# Power_Supply.net
KiCad netlist of a schematic drawn in Altium Designer
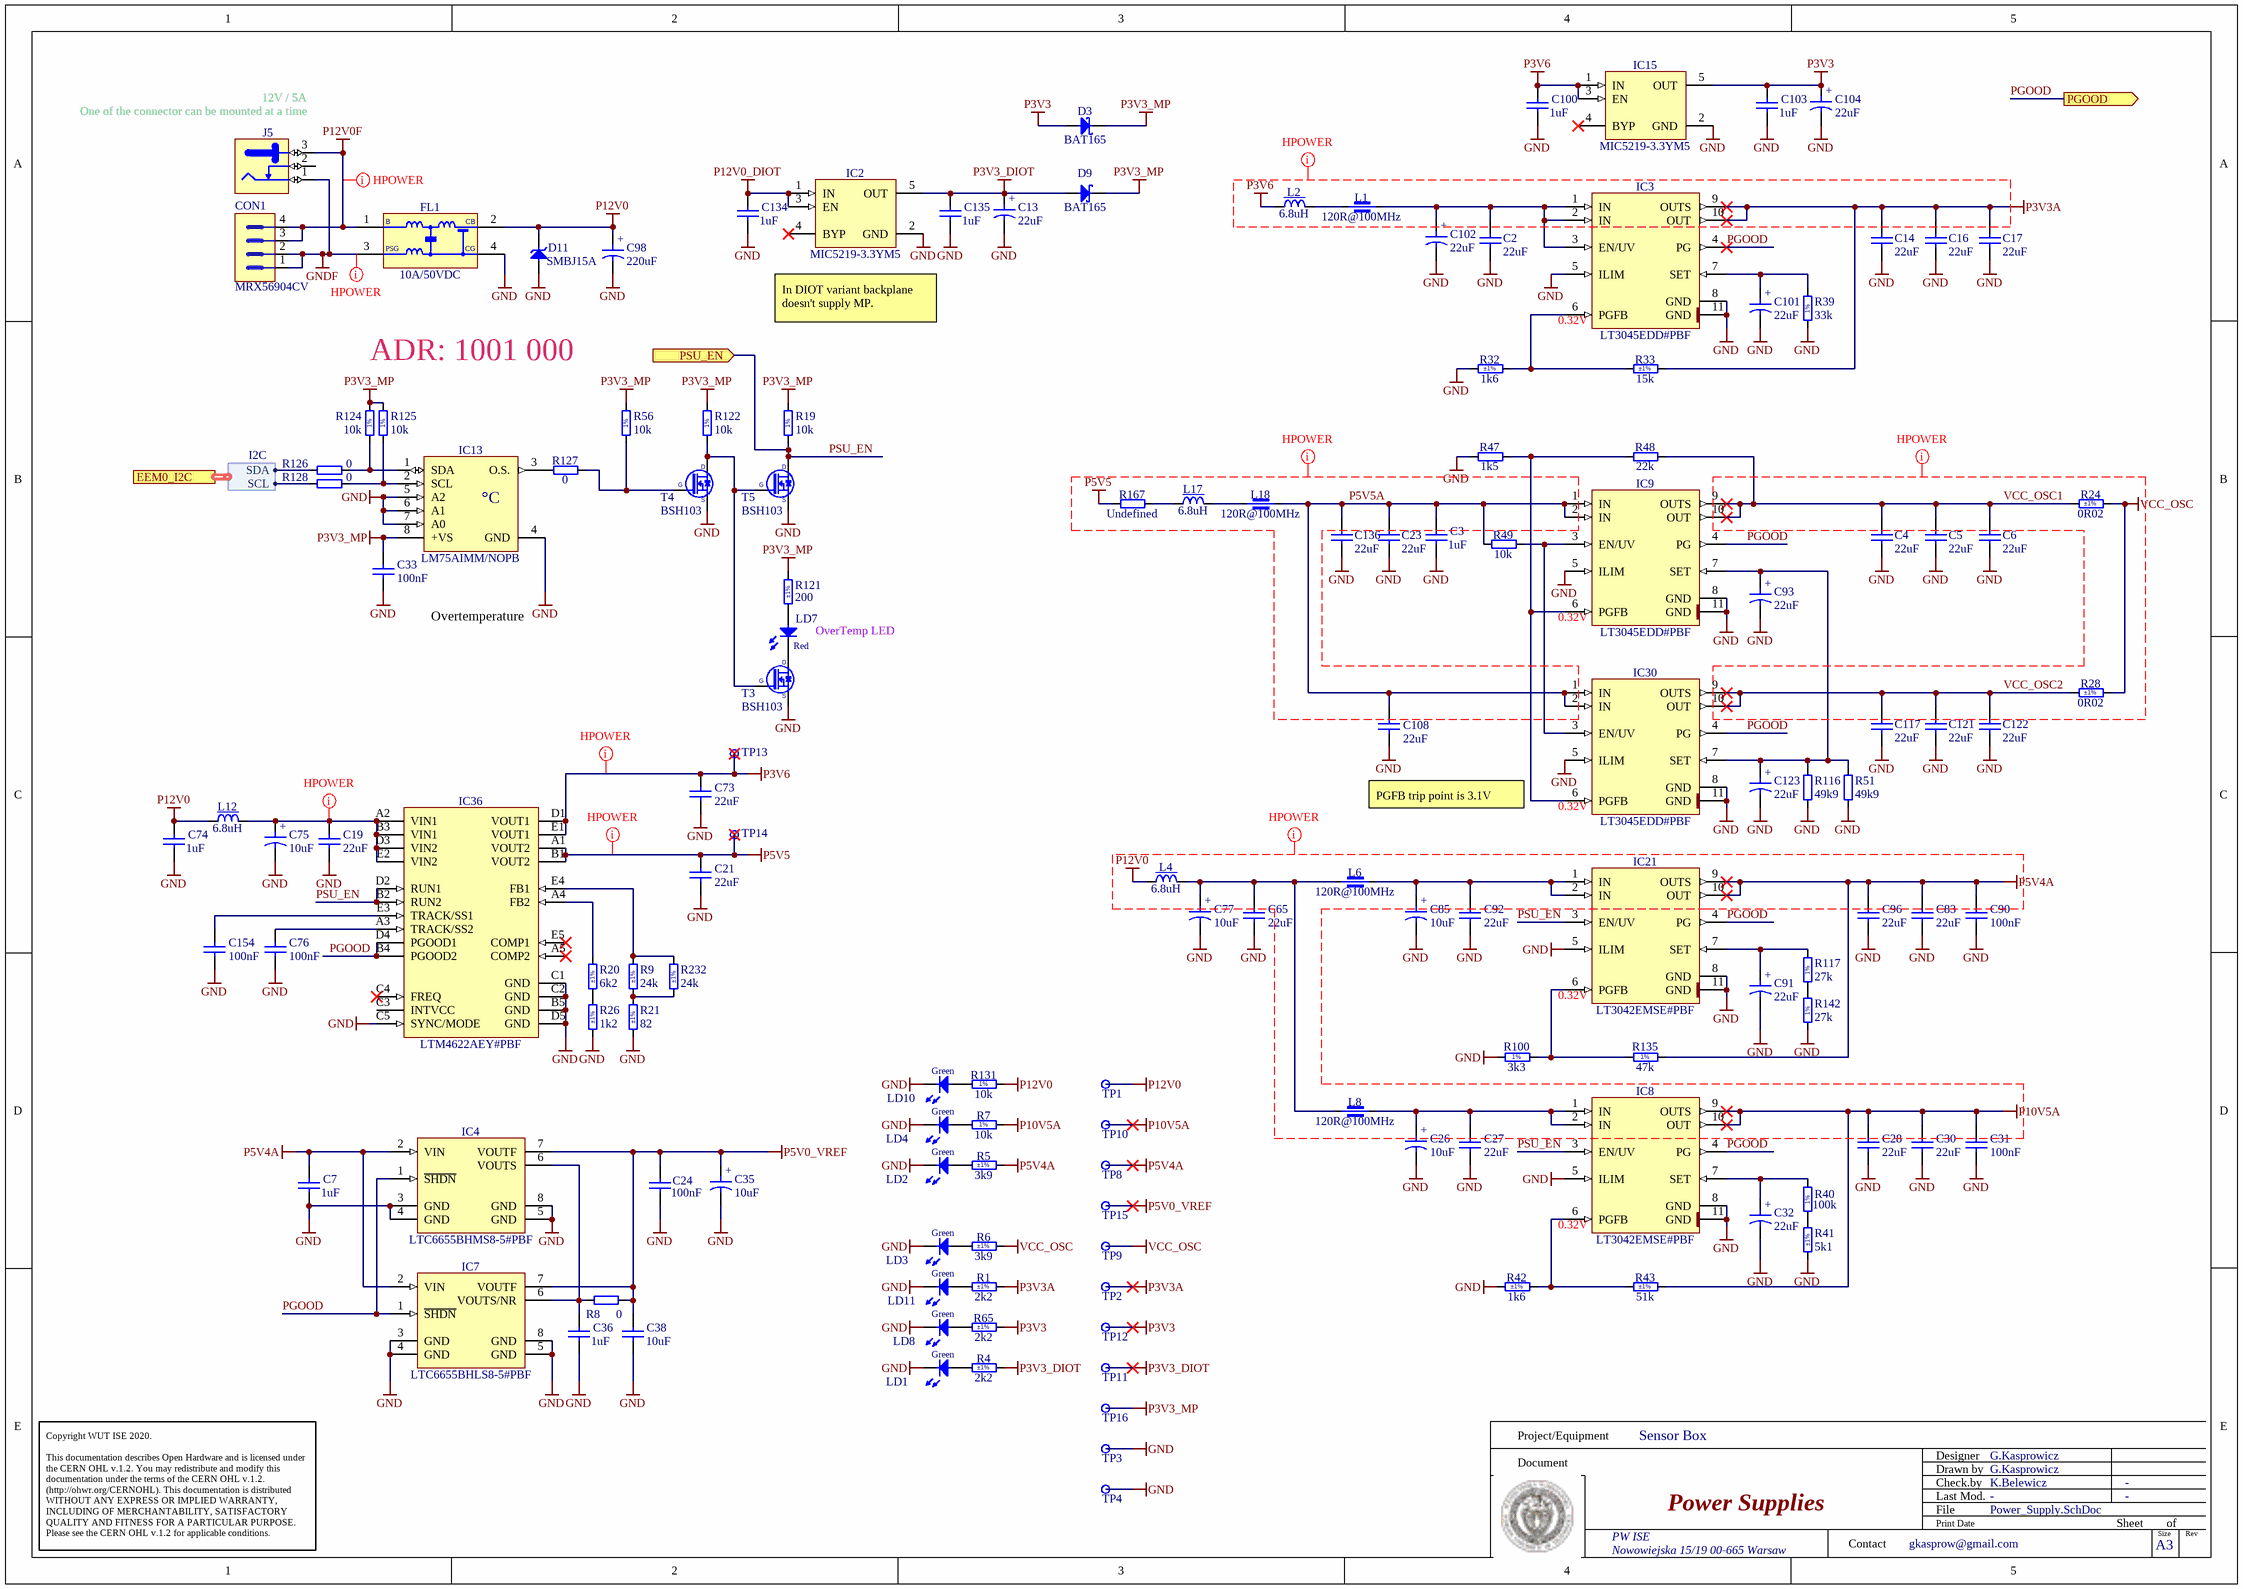
[diagram p0: Power_Supply.SchDoc]

(export (version "E")
  (design (tool "Eeschema 10.0.6"))
  (components
    (comp (ref "C2")
      (value "22uF")
      (footprint "CAPC2012X135N")
      (description "Non-polarised capacitor")
      (fields
        (field (name "PART NUMBER") "CC0805_22UF_16V_10%_X5R")
        (field (name "VOLTAGE") "16V")
        (field (name "AUTHOR") "CERN DEM JLC")
      )
      (libsource (lib "Capacitors") (part "Capacitor - non polarized"))
    )
    (comp (ref "C3")
      (value "1uF")
      (footprint "CAPC1005X55N")
      (description "Non-polarised capacitor")
      (fields
        (field (name "PART NUMBER") "CC0402_1UF_16V_10%_X5R")
        (field (name "VOLTAGE") "16V")
        (field (name "AUTHOR") "CERN DEM JLC")
      )
      (libsource (lib "Capacitors") (part "Capacitor - non polarized"))
    )
    (comp (ref "C4")
      (value "22uF")
      (footprint "CAPC2012X135N")
      (description "Non-polarised capacitor")
      (fields
        (field (name "PART NUMBER") "CC0805_22UF_16V_10%_X5R")
        (field (name "VOLTAGE") "16V")
        (field (name "AUTHOR") "CERN DEM JLC")
      )
      (libsource (lib "Capacitors") (part "Capacitor - non polarized"))
    )
    (comp (ref "C5")
      (value "22uF")
      (footprint "CAPC2012X135N")
      (description "Non-polarised capacitor")
      (fields
        (field (name "PART NUMBER") "CC0805_22UF_16V_10%_X5R")
        (field (name "VOLTAGE") "16V")
        (field (name "AUTHOR") "CERN DEM JLC")
      )
      (libsource (lib "Capacitors") (part "Capacitor - non polarized"))
    )
    (comp (ref "C6")
      (value "22uF")
      (footprint "CAPC2012X135N")
      (description "Non-polarised capacitor")
      (fields
        (field (name "PART NUMBER") "CC0805_22UF_16V_10%_X5R")
        (field (name "VOLTAGE") "16V")
        (field (name "AUTHOR") "CERN DEM JLC")
      )
      (libsource (lib "Capacitors") (part "Capacitor - non polarized"))
    )
    (comp (ref "C7")
      (value "1uF")
      (footprint "CAPC1005X55N")
      (description "Non-polarised capacitor")
      (fields
        (field (name "PART NUMBER") "CC0402_1UF_16V_10%_X5R")
        (field (name "VOLTAGE") "16V")
        (field (name "AUTHOR") "CERN DEM JLC")
      )
      (libsource (lib "Capacitors") (part "Capacitor - non polarized"))
    )
    (comp (ref "C13")
      (value "22uF")
      (footprint "CAPMP3528X210N")
      (description "Polarised capacitor")
      (fields
        (field (name "PART NUMBER") "CTE3528-21_22UF_10V_10%_LESR0700")
        (field (name "VOLTAGE") "10V")
        (field (name "AUTHOR") "CERN DEM JLC")
      )
      (libsource (lib "Capacitors") (part "Capacitor - polarized"))
    )
    (comp (ref "C14")
      (value "22uF")
      (footprint "CAPC2012X135N")
      (description "Non-polarised capacitor")
      (fields
        (field (name "PART NUMBER") "CC0805_22UF_16V_10%_X5R")
        (field (name "VOLTAGE") "16V")
        (field (name "AUTHOR") "CERN DEM JLC")
      )
      (libsource (lib "Capacitors") (part "Capacitor - non polarized"))
    )
    (comp (ref "C16")
      (value "22uF")
      (footprint "CAPC2012X135N")
      (description "Non-polarised capacitor")
      (fields
        (field (name "PART NUMBER") "CC0805_22UF_16V_10%_X5R")
        (field (name "VOLTAGE") "16V")
        (field (name "AUTHOR") "CERN DEM JLC")
      )
      (libsource (lib "Capacitors") (part "Capacitor - non polarized"))
    )
    (comp (ref "C17")
      (value "22uF")
      (footprint "CAPC2012X135N")
      (description "Non-polarised capacitor")
      (fields
        (field (name "PART NUMBER") "CC0805_22UF_16V_10%_X5R")
        (field (name "VOLTAGE") "16V")
        (field (name "AUTHOR") "CERN DEM JLC")
      )
      (libsource (lib "Capacitors") (part "Capacitor - non polarized"))
    )
    (comp (ref "C19")
      (value "22uF")
      (footprint "CAPC2012X135N")
      (description "Non-polarised capacitor")
      (fields
        (field (name "PART NUMBER") "CC0805_22UF_16V_10%_X5R")
        (field (name "VOLTAGE") "16V")
        (field (name "AUTHOR") "CERN DEM JLC")
      )
      (libsource (lib "Capacitors") (part "Capacitor - non polarized"))
    )
    (comp (ref "C21")
      (value "22uF")
      (footprint "CAPC2012X135N")
      (description "Non-polarised capacitor")
      (fields
        (field (name "PART NUMBER") "CC0805_22UF_16V_10%_X5R")
        (field (name "VOLTAGE") "16V")
        (field (name "AUTHOR") "CERN DEM JLC")
      )
      (libsource (lib "Capacitors") (part "Capacitor - non polarized"))
    )
    (comp (ref "C23")
      (value "22uF")
      (footprint "CAPC2012X135N")
      (description "Non-polarised capacitor")
      (fields
        (field (name "PART NUMBER") "CC0805_22UF_16V_10%_X5R")
        (field (name "VOLTAGE") "16V")
        (field (name "AUTHOR") "CERN DEM JLC")
      )
      (libsource (lib "Capacitors") (part "Capacitor - non polarized"))
    )
    (comp (ref "C24")
      (value "100nF")
      (footprint "CAPC1005X55N")
      (description "Non-polarised capacitor")
      (fields
        (field (name "PART NUMBER") "CC0402_100NF_16V_10%_X5R")
        (field (name "VOLTAGE") "16V")
        (field (name "AUTHOR") "CERN DEM JLC")
      )
      (libsource (lib "Capacitors") (part "Capacitor - non polarized"))
    )
    (comp (ref "C26")
      (value "10uF")
      (footprint "CAPMP3216X180N")
      (description "Polarised capacitor")
      (fields
        (field (name "PART NUMBER") "CTE3216-18_10UF_16V_20%_AVX_TCJ")
        (field (name "VOLTAGE") "16V")
        (field (name "AUTHOR") "CERN DEM JLC")
      )
      (libsource (lib "Capacitors") (part "Capacitor - polarized"))
    )
    (comp (ref "C27")
      (value "22uF")
      (footprint "CAPC2012X135N")
      (description "Non-polarised capacitor")
      (fields
        (field (name "PART NUMBER") "CC0805_22UF_16V_10%_X5R")
        (field (name "VOLTAGE") "16V")
        (field (name "AUTHOR") "CERN DEM JLC")
      )
      (libsource (lib "Capacitors") (part "Capacitor - non polarized"))
    )
    (comp (ref "C28")
      (value "22uF")
      (footprint "CAPC2012X135N")
      (description "Non-polarised capacitor")
      (fields
        (field (name "PART NUMBER") "CC0805_22UF_16V_10%_X5R")
        (field (name "VOLTAGE") "16V")
        (field (name "AUTHOR") "CERN DEM JLC")
      )
      (libsource (lib "Capacitors") (part "Capacitor - non polarized"))
    )
    (comp (ref "C30")
      (value "22uF")
      (footprint "CAPC2012X135N")
      (description "Non-polarised capacitor")
      (fields
        (field (name "PART NUMBER") "CC0805_22UF_16V_10%_X5R")
        (field (name "VOLTAGE") "16V")
        (field (name "AUTHOR") "CERN DEM JLC")
      )
      (libsource (lib "Capacitors") (part "Capacitor - non polarized"))
    )
    (comp (ref "C31")
      (value "100nF")
      (footprint "CAPC1005X55N")
      (description "Non-polarised capacitor")
      (fields
        (field (name "PART NUMBER") "CC0402_100NF_16V_10%_X5R")
        (field (name "VOLTAGE") "16V")
        (field (name "AUTHOR") "CERN DEM JLC")
      )
      (libsource (lib "Capacitors") (part "Capacitor - non polarized"))
    )
    (comp (ref "C32")
      (value "22uF")
      (footprint "CAPMP3528X210N")
      (description "Polarised capacitor")
      (fields
        (field (name "PART NUMBER") "CTE3528-21_22UF_10V_10%_LESR0700")
        (field (name "VOLTAGE") "10V")
        (field (name "AUTHOR") "CERN DEM JLC")
      )
      (libsource (lib "Capacitors") (part "Capacitor - polarized"))
    )
    (comp (ref "C33")
      (value "100nF")
      (footprint "CAPC1005X55N")
      (description "Non-polarised capacitor")
      (fields
        (field (name "PART NUMBER") "CC0402_100NF_16V_10%_X5R")
        (field (name "VOLTAGE") "16V")
        (field (name "AUTHOR") "CERN DEM JLC")
      )
      (libsource (lib "Capacitors") (part "Capacitor - non polarized"))
    )
    (comp (ref "C35")
      (value "10uF")
      (footprint "CAPMP3216X180N")
      (description "Polarised capacitor")
      (fields
        (field (name "PART NUMBER") "CTE3216-18_10UF_16V_20%_AVX_TCJ")
        (field (name "VOLTAGE") "16V")
        (field (name "AUTHOR") "CERN DEM JLC")
      )
      (libsource (lib "Capacitors") (part "Capacitor - polarized"))
    )
    (comp (ref "C36")
      (value "1uF")
      (footprint "CAPC1005X55N")
      (description "Non-polarised capacitor")
      (fields
        (field (name "PART NUMBER") "CC0402_1UF_16V_10%_X5R")
        (field (name "VOLTAGE") "16V")
        (field (name "AUTHOR") "CERN DEM JLC")
      )
      (libsource (lib "Capacitors") (part "Capacitor - non polarized"))
    )
    (comp (ref "C38")
      (value "10uF")
      (footprint "CAPC1608X80N")
      (description "Non-polarised capacitor")
      (fields
        (field (name "PART NUMBER") "CC0603_10UF_16V_20%_X5R")
        (field (name "VOLTAGE") "16V")
        (field (name "AUTHOR") "CERN DEM MR")
      )
      (libsource (lib "Capacitors") (part "Capacitor - non polarized"))
    )
    (comp (ref "C65")
      (value "22uF")
      (footprint "CAPC2012X135N")
      (description "Non-polarised capacitor")
      (fields
        (field (name "PART NUMBER") "CC0805_22UF_16V_10%_X5R")
        (field (name "VOLTAGE") "16V")
        (field (name "AUTHOR") "CERN DEM JLC")
      )
      (libsource (lib "Capacitors") (part "Capacitor - non polarized"))
    )
    (comp (ref "C73")
      (value "22uF")
      (footprint "CAPC2012X135N")
      (description "Non-polarised capacitor")
      (fields
        (field (name "PART NUMBER") "CC0805_22UF_16V_10%_X5R")
        (field (name "VOLTAGE") "16V")
        (field (name "AUTHOR") "CERN DEM JLC")
      )
      (libsource (lib "Capacitors") (part "Capacitor - non polarized"))
    )
    (comp (ref "C74")
      (value "1uF")
      (footprint "CAPC1005X55N")
      (description "Non-polarised capacitor")
      (fields
        (field (name "PART NUMBER") "CC0402_1UF_16V_10%_X5R")
        (field (name "VOLTAGE") "16V")
        (field (name "AUTHOR") "CERN DEM JLC")
      )
      (libsource (lib "Capacitors") (part "Capacitor - non polarized"))
    )
    (comp (ref "C75")
      (value "10uF")
      (footprint "CAPMP3216X180N")
      (description "Polarised capacitor")
      (fields
        (field (name "PART NUMBER") "CTE3216-18_10UF_16V_20%_AVX_TCJ")
        (field (name "VOLTAGE") "16V")
        (field (name "AUTHOR") "CERN DEM JLC")
      )
      (libsource (lib "Capacitors") (part "Capacitor - polarized"))
    )
    (comp (ref "C76")
      (value "100nF")
      (footprint "CAPC1005X55N")
      (description "Non-polarised capacitor")
      (fields
        (field (name "PART NUMBER") "CC0402_100NF_16V_10%_X5R")
        (field (name "VOLTAGE") "16V")
        (field (name "AUTHOR") "CERN DEM JLC")
      )
      (libsource (lib "Capacitors") (part "Capacitor - non polarized"))
    )
    (comp (ref "C77")
      (value "10uF")
      (footprint "CAPMP3216X180N")
      (description "Polarised capacitor")
      (fields
        (field (name "PART NUMBER") "CTE3216-18_10UF_16V_20%_AVX_TCJ")
        (field (name "VOLTAGE") "16V")
        (field (name "AUTHOR") "CERN DEM JLC")
      )
      (libsource (lib "Capacitors") (part "Capacitor - polarized"))
    )
    (comp (ref "C83")
      (value "22uF")
      (footprint "CAPC2012X135N")
      (description "Non-polarised capacitor")
      (fields
        (field (name "PART NUMBER") "CC0805_22UF_16V_10%_X5R")
        (field (name "VOLTAGE") "16V")
        (field (name "AUTHOR") "CERN DEM JLC")
      )
      (libsource (lib "Capacitors") (part "Capacitor - non polarized"))
    )
    (comp (ref "C85")
      (value "10uF")
      (footprint "CAPMP3216X180N")
      (description "Polarised capacitor")
      (fields
        (field (name "PART NUMBER") "CTE3216-18_10UF_16V_20%_AVX_TCJ")
        (field (name "VOLTAGE") "16V")
        (field (name "AUTHOR") "CERN DEM JLC")
      )
      (libsource (lib "Capacitors") (part "Capacitor - polarized"))
    )
    (comp (ref "C90")
      (value "100nF")
      (footprint "CAPC1005X55N")
      (description "Non-polarised capacitor")
      (fields
        (field (name "PART NUMBER") "CC0402_100NF_16V_10%_X5R")
        (field (name "VOLTAGE") "16V")
        (field (name "AUTHOR") "CERN DEM JLC")
      )
      (libsource (lib "Capacitors") (part "Capacitor - non polarized"))
    )
    (comp (ref "C91")
      (value "22uF")
      (footprint "CAPMP3528X210N")
      (description "Polarised capacitor")
      (fields
        (field (name "PART NUMBER") "CTE3528-21_22UF_10V_10%_LESR0700")
        (field (name "VOLTAGE") "10V")
        (field (name "AUTHOR") "CERN DEM JLC")
      )
      (libsource (lib "Capacitors") (part "Capacitor - polarized"))
    )
    (comp (ref "C92")
      (value "22uF")
      (footprint "CAPC2012X135N")
      (description "Non-polarised capacitor")
      (fields
        (field (name "PART NUMBER") "CC0805_22UF_16V_10%_X5R")
        (field (name "VOLTAGE") "16V")
        (field (name "AUTHOR") "CERN DEM JLC")
      )
      (libsource (lib "Capacitors") (part "Capacitor - non polarized"))
    )
    (comp (ref "C93")
      (value "22uF")
      (footprint "CAPMP3528X210N")
      (description "Polarised capacitor")
      (fields
        (field (name "PART NUMBER") "CTE3528-21_22UF_10V_10%_LESR0700")
        (field (name "VOLTAGE") "10V")
        (field (name "AUTHOR") "CERN DEM JLC")
      )
      (libsource (lib "Capacitors") (part "Capacitor - polarized"))
    )
    (comp (ref "C96")
      (value "22uF")
      (footprint "CAPC2012X135N")
      (description "Non-polarised capacitor")
      (fields
        (field (name "PART NUMBER") "CC0805_22UF_16V_10%_X5R")
        (field (name "VOLTAGE") "16V")
        (field (name "AUTHOR") "CERN DEM JLC")
      )
      (libsource (lib "Capacitors") (part "Capacitor - non polarized"))
    )
    (comp (ref "C98")
      (value "220uF")
      (footprint "CAPAE830X620N")
      (description "Polarised capacitor")
      (fields
        (field (name "PART NUMBER") "CAE830-620_220UF_16V_20%")
        (field (name "VOLTAGE") "16V")
        (field (name "AUTHOR") "CERN DEM JLC")
      )
      (libsource (lib "Capacitors") (part "Capacitor - polarized"))
    )
    (comp (ref "C100")
      (value "1uF")
      (footprint "CAPC1005X55N")
      (description "Non-polarised capacitor")
      (fields
        (field (name "PART NUMBER") "CC0402_1UF_16V_10%_X5R")
        (field (name "VOLTAGE") "16V")
        (field (name "AUTHOR") "CERN DEM JLC")
      )
      (libsource (lib "Capacitors") (part "Capacitor - non polarized"))
    )
    (comp (ref "C101")
      (value "22uF")
      (footprint "CAPMP3528X210N")
      (description "Polarised capacitor")
      (fields
        (field (name "PART NUMBER") "CTE3528-21_22UF_10V_10%_LESR0700")
        (field (name "VOLTAGE") "10V")
        (field (name "AUTHOR") "CERN DEM JLC")
      )
      (libsource (lib "Capacitors") (part "Capacitor - polarized"))
    )
    (comp (ref "C102")
      (value "22uF")
      (footprint "CAPMP3528X210N")
      (description "Polarised capacitor")
      (fields
        (field (name "PART NUMBER") "CTE3528-21_22UF_10V_10%_LESR0700")
        (field (name "VOLTAGE") "10V")
        (field (name "AUTHOR") "CERN DEM JLC")
      )
      (libsource (lib "Capacitors") (part "Capacitor - polarized"))
    )
    (comp (ref "C103")
      (value "1uF")
      (footprint "CAPC1005X55N")
      (description "Non-polarised capacitor")
      (fields
        (field (name "PART NUMBER") "CC0402_1UF_16V_10%_X5R")
        (field (name "VOLTAGE") "16V")
        (field (name "AUTHOR") "CERN DEM JLC")
      )
      (libsource (lib "Capacitors") (part "Capacitor - non polarized"))
    )
    (comp (ref "C104")
      (value "22uF")
      (footprint "CAPMP3528X210N")
      (description "Polarised capacitor")
      (fields
        (field (name "PART NUMBER") "CTE3528-21_22UF_10V_10%_LESR0700")
        (field (name "VOLTAGE") "10V")
        (field (name "AUTHOR") "CERN DEM JLC")
      )
      (libsource (lib "Capacitors") (part "Capacitor - polarized"))
    )
    (comp (ref "C108")
      (value "22uF")
      (footprint "CAPC2012X135N")
      (description "Non-polarised capacitor")
      (fields
        (field (name "PART NUMBER") "CC0805_22UF_16V_10%_X5R")
        (field (name "VOLTAGE") "16V")
        (field (name "AUTHOR") "CERN DEM JLC")
      )
      (libsource (lib "Capacitors") (part "Capacitor - non polarized"))
    )
    (comp (ref "C117")
      (value "22uF")
      (footprint "CAPC2012X135N")
      (description "Non-polarised capacitor")
      (fields
        (field (name "PART NUMBER") "CC0805_22UF_16V_10%_X5R")
        (field (name "VOLTAGE") "16V")
        (field (name "AUTHOR") "CERN DEM JLC")
      )
      (libsource (lib "Capacitors") (part "Capacitor - non polarized"))
    )
    (comp (ref "C121")
      (value "22uF")
      (footprint "CAPC2012X135N")
      (description "Non-polarised capacitor")
      (fields
        (field (name "PART NUMBER") "CC0805_22UF_16V_10%_X5R")
        (field (name "VOLTAGE") "16V")
        (field (name "AUTHOR") "CERN DEM JLC")
      )
      (libsource (lib "Capacitors") (part "Capacitor - non polarized"))
    )
    (comp (ref "C122")
      (value "22uF")
      (footprint "CAPC2012X135N")
      (description "Non-polarised capacitor")
      (fields
        (field (name "PART NUMBER") "CC0805_22UF_16V_10%_X5R")
        (field (name "VOLTAGE") "16V")
        (field (name "AUTHOR") "CERN DEM JLC")
      )
      (libsource (lib "Capacitors") (part "Capacitor - non polarized"))
    )
    (comp (ref "C123")
      (value "22uF")
      (footprint "CAPMP3528X210N")
      (description "Polarised capacitor")
      (fields
        (field (name "PART NUMBER") "CTE3528-21_22UF_10V_10%_LESR0700")
        (field (name "VOLTAGE") "10V")
        (field (name "AUTHOR") "CERN DEM JLC")
      )
      (libsource (lib "Capacitors") (part "Capacitor - polarized"))
    )
    (comp (ref "C134")
      (value "1uF")
      (footprint "CAPC1005X55N")
      (description "Non-polarised capacitor")
      (fields
        (field (name "PART NUMBER") "CC0402_1UF_16V_10%_X5R")
        (field (name "VOLTAGE") "16V")
        (field (name "AUTHOR") "CERN DEM JLC")
      )
      (libsource (lib "Capacitors") (part "Capacitor - non polarized"))
    )
    (comp (ref "C135")
      (value "1uF")
      (footprint "CAPC1005X55N")
      (description "Non-polarised capacitor")
      (fields
        (field (name "PART NUMBER") "CC0402_1UF_16V_10%_X5R")
        (field (name "VOLTAGE") "16V")
        (field (name "AUTHOR") "CERN DEM JLC")
      )
      (libsource (lib "Capacitors") (part "Capacitor - non polarized"))
    )
    (comp (ref "C136")
      (value "22uF")
      (footprint "CAPC2012X135N")
      (description "Non-polarised capacitor")
      (fields
        (field (name "PART NUMBER") "CC0805_22UF_16V_10%_X5R")
        (field (name "VOLTAGE") "16V")
        (field (name "AUTHOR") "CERN DEM JLC")
      )
      (libsource (lib "Capacitors") (part "Capacitor - non polarized"))
    )
    (comp (ref "C154")
      (value "100nF")
      (footprint "CAPC1005X55N")
      (description "Non-polarised capacitor")
      (fields
        (field (name "PART NUMBER") "CC0402_100NF_16V_10%_X5R")
        (field (name "VOLTAGE") "16V")
        (field (name "AUTHOR") "CERN DEM JLC")
      )
      (libsource (lib "Capacitors") (part "Capacitor - non polarized"))
    )
    (comp (ref "CON1")
      (value "MRX56904CV")
      (footprint "MRX56904CV")
      (description "4.2mm cripm terminal header")
      (fields (field (name "MANUFACTURER") "Molex"))
      (libsource (lib "LIBRARY_SCH") (part "CON_CRIMP_4.2mm_RA_4"))
    )
    (comp (ref "D3")
      (value "BAT165")
      (footprint "SOD2512X110N")
      (description "Schottky Diode")
      (fields
        (field (name "VOLTAGE") "40V")
        (field (name "POWER") "750mA")
        (field (name "AUTHOR") "CERN DEM JLC")
      )
      (libsource (lib "ICs And Semiconductors") (part "Diode Schottky"))
    )
    (comp (ref "D9")
      (value "BAT165")
      (footprint "SOD2512X110N")
      (description "Schottky Diode")
      (fields
        (field (name "MANUFACTURER") "INFINEON")
        (field (name "VOLTAGE") "40V")
        (field (name "AUTHOR") "CERN DEM JLC")
      )
      (libsource (lib "ICs And Semiconductors") (part "Diode Schottky"))
    )
    (comp (ref "D11")
      (value "SMBJ15A")
      (footprint "DIOM5336X265N")
      (description "Zener Diode")
      (fields
        (field (name "VOLTAGE") "15V")
        (field (name "POWER") "600W")
        (field (name "AUTHOR") "CERN DEM JLC")
      )
      (libsource (lib "ICs And Semiconductors") (part "Diode Zener"))
    )
    (comp (ref "FL1")
      (value "10A/50VDC")
      (footprint "FIL_MURATA_BNX02")
      (description "Block Type EMIFIL (LC Combined)")
      (fields
        (field (name "PART NUMBER") "FIL_MURATA_BNX022-01L")
        (field (name "MANUFACTURER") "MURATA")
        (field (name "AUTHOR") "CERN DEM JLC")
      )
      (libsource (lib "Inductors & Transformers") (part "FIL_MURATA_BNX02"))
    )
    (comp (ref "IC2")
      (value "MIC5219-3.3YM5")
      (footprint "SOT95P280X145-5N")
      (description "500mA Peak Output LDO Regulator")
      (fields (field (name "MANUFACTURER") "MICROCHIP TECHNOLOGY") (field (name "AUTHOR") "CERN DEM WB"))
      (libsource (lib "ICs And Semiconductors") (part "MIC5219-X.XYM5"))
    )
    (comp (ref "IC3")
      (value "LT3045EDD#PBF")
      (footprint "SON50P300X300X80-11N-R175X248")
      (description "20V, 500mA, Ultralow Noise, Ultrahigh PSRR Linear Regulator")
      (fields (field (name "MANUFACTURER") "LINEAR TECHNOLOGY") (field (name "AUTHOR") "CERN DEM JLC"))
      (libsource (lib "ICs And Semiconductors") (part "LT3045EDD"))
    )
    (comp (ref "IC4")
      (value "LTC6655BHMS8-5#PBF")
      (footprint "SOP65P490X110-8N")
      (description "0.25ppm Noise, Low Drift Precision Buffered Voltage Reference")
      (fields (field (name "MANUFACTURER") "LINEAR TECHNOLOGY") (field (name "AUTHOR") "CERN DEM JLC"))
      (libsource (lib "ICs And Semiconductors") (part "LTC6655"))
    )
    (comp (ref "IC7")
      (value "LTC6655BHLS8-5#PBF")
      (footprint "8-CLCC")
      (description "5.0V, 1uA Precision Voltage Reference")
      (fields (field (name "MANUFACTURER") "LINEAR TECHNOLOGY") (field (name "AUTHOR") "GK"))
      (libsource (lib "Sampler") (part "REF_LTC6655CHLS8-4.096"))
    )
    (comp (ref "IC8")
      (value "LT3042EMSE#PBF")
      (footprint "SOP50P490X110-11N-R168X198")
      (description "20V, 200mA, Ultralow Noise, Ultrahigh PSRR RF Linear Regulator")
      (fields (field (name "MANUFACTURER") "LINEAR TECHNOLOGY") (field (name "AUTHOR") "CERN DEM MR"))
      (libsource (lib "ICs And Semiconductors") (part "LT3042"))
    )
    (comp (ref "IC9")
      (value "LT3045EDD#PBF")
      (footprint "SON50P300X300X80-11N-R175X248")
      (description "20V, 500mA, Ultralow Noise, Ultrahigh PSRR Linear Regulator")
      (fields (field (name "MANUFACTURER") "LINEAR TECHNOLOGY") (field (name "AUTHOR") "CERN DEM JLC"))
      (libsource (lib "ICs And Semiconductors") (part "LT3045EDD"))
    )
    (comp (ref "IC13")
      (value "LM75AIMM/NOPB")
      (footprint "SOP65P490X109-8N")
      (description "Digital Temperature Sensor and Thermal Watchdog with Two-Wire Interface")
      (fields (field (name "MANUFACTURER") "TEXAS INSTRUMENTS") (field (name "AUTHOR") "CERN DEM JLC"))
      (libsource (lib "ICs And Semiconductors") (part "LM75"))
    )
    (comp (ref "IC15")
      (value "MIC5219-3.3YM5")
      (footprint "SOT95P280X145-5N")
      (description "500mA Peak Output LDO Regulator")
      (fields (field (name "MANUFACTURER") "MICROCHIP TECHNOLOGY") (field (name "AUTHOR") "CERN DEM WB"))
      (libsource (lib "ICs And Semiconductors") (part "MIC5219-X.XYM5"))
    )
    (comp (ref "IC21")
      (value "LT3042EMSE#PBF")
      (footprint "SOP50P490X110-11N-R168X198")
      (description "20V, 200mA, Ultralow Noise, Ultrahigh PSRR RF Linear Regulator")
      (fields (field (name "MANUFACTURER") "LINEAR TECHNOLOGY") (field (name "AUTHOR") "CERN DEM MR"))
      (libsource (lib "ICs And Semiconductors") (part "LT3042"))
    )
    (comp (ref "IC30")
      (value "LT3045EDD#PBF")
      (footprint "SON50P300X300X80-11N-R175X248")
      (description "20V, 500mA, Ultralow Noise, Ultrahigh PSRR Linear Regulator")
      (fields (field (name "MANUFACTURER") "LINEAR TECHNOLOGY") (field (name "AUTHOR") "CERN DEM JLC"))
      (libsource (lib "ICs And Semiconductors") (part "LT3045EDD"))
    )
    (comp (ref "IC36")
      (value "LTM4622AEY#PBF")
      (footprint "BGA25C127P5X5_625X625X262")
      (description "3.6V-20V To 1.5V-12V, Dual 2A or Single 4A  Ultrathin Step-Down DC/DC µModule Regulator")
      (fields (field (name "MANUFACTURER") "LINEAR TECHNOLOGY") (field (name "AUTHOR") "CERN DEM MR"))
      (libsource (lib "ICs And Semiconductors") (part "LTM4622A"))
    )
    (comp (ref "J5")
      (value "Jack")
      (footprint "SWITCHCRAFT_L712RA")
      (description "24V /3. 5A, 2.1mm Diameter Pin, SMD DC Power Supply Connector With  Break Contact")
      (fields
        (field (name "PART NUMBER") "SWITCHCRAFT_L712RA")
        (field (name "MANUFACTURER") "SWITCHCRAFT")
        (field (name "AUTHOR") "GK")
      )
      (libsource (lib "LIBRARY_SCH") (part "CON_DC_5A_THT_RA"))
    )
    (comp (ref "L1")
      (value "120R@100MHz")
      (footprint "INDC1608X65N")
      (fields
        (field (name "PART NUMBER") "IND0603_MURATA_BLM18SG121TN1D")
        (field (name "POWER") "3A")
        (field (name "TOLERANCE") "±25%")
        (field (name "AUTHOR") "CERN DEM JLC")
      )
      (libsource (lib "Inductors & Transformers") (part "Ferrite Bead"))
    )
    (comp (ref "L2")
      (value "6.8uH")
      (footprint "IND_COILCRAFT_XAL4030")
      (description "Inductor With Core")
      (fields
        (field (name "PART NUMBER") "IND_6.8UH_20%_COILCRAFT_XAL4030")
        (field (name "POWER") "3A")
        (field (name "AUTHOR") "CERN DEM MR")
      )
      (libsource (lib "Inductors & Transformers") (part "Inductor With Magnetic core"))
    )
    (comp (ref "L4")
      (value "6.8uH")
      (footprint "IND_COILCRAFT_XAL4030")
      (description "Inductor With Core")
      (fields
        (field (name "PART NUMBER") "IND_6.8UH_20%_COILCRAFT_XAL4030")
        (field (name "POWER") "3A")
        (field (name "AUTHOR") "CERN DEM MR")
      )
      (libsource (lib "Inductors & Transformers") (part "Inductor With Magnetic core"))
    )
    (comp (ref "L6")
      (value "120R@100MHz")
      (footprint "INDC1608X65N")
      (fields
        (field (name "PART NUMBER") "IND0603_MURATA_BLM18SG121TN1D")
        (field (name "POWER") "3A")
        (field (name "TOLERANCE") "±25%")
        (field (name "AUTHOR") "CERN DEM JLC")
      )
      (libsource (lib "Inductors & Transformers") (part "Ferrite Bead"))
    )
    (comp (ref "L8")
      (value "120R@100MHz")
      (footprint "INDC1608X65N")
      (fields
        (field (name "PART NUMBER") "IND0603_MURATA_BLM18SG121TN1D")
        (field (name "POWER") "3A")
        (field (name "TOLERANCE") "±25%")
        (field (name "AUTHOR") "CERN DEM JLC")
      )
      (libsource (lib "Inductors & Transformers") (part "Ferrite Bead"))
    )
    (comp (ref "L12")
      (value "6.8uH")
      (footprint "IND_COILCRAFT_XAL4030")
      (description "Inductor With Core")
      (fields
        (field (name "PART NUMBER") "IND_6.8UH_20%_COILCRAFT_XAL4030")
        (field (name "POWER") "3A")
        (field (name "AUTHOR") "CERN DEM MR")
      )
      (libsource (lib "Inductors & Transformers") (part "Inductor With Magnetic core"))
    )
    (comp (ref "L17")
      (value "6.8uH")
      (footprint "IND_COILCRAFT_XAL4030")
      (description "Inductor With Core")
      (fields
        (field (name "PART NUMBER") "IND_6.8UH_20%_COILCRAFT_XAL4030")
        (field (name "POWER") "3A")
        (field (name "AUTHOR") "CERN DEM MR")
      )
      (libsource (lib "Inductors & Transformers") (part "Inductor With Magnetic core"))
    )
    (comp (ref "L18")
      (value "120R@100MHz")
      (footprint "INDC1608X65N")
      (fields
        (field (name "PART NUMBER") "IND0603_MURATA_BLM18SG121TN1D")
        (field (name "POWER") "3A")
        (field (name "TOLERANCE") "±25%")
        (field (name "AUTHOR") "CERN DEM JLC")
      )
      (libsource (lib "Inductors & Transformers") (part "Ferrite Bead"))
    )
    (comp (ref "LD1")
      (value "Green")
      (footprint "LED_KINGBRIGHT_KPH-1608CGCK")
      (description "LED Green 1C 2A")
      (fields
        (field (name "PART NUMBER") "LED_KINGBRIGHT_KPH-1608CGCK")
        (field (name "MANUFACTURER") "KINGBRIGHT")
        (field (name "AUTHOR") "CERN DEM JLC")
      )
      (libsource (lib "ICs And Semiconductors") (part "LED Green 1C 2A"))
    )
    (comp (ref "LD2")
      (value "Green")
      (footprint "LED_KINGBRIGHT_KPH-1608CGCK")
      (description "LED Green 1C 2A")
      (fields
        (field (name "PART NUMBER") "LED_KINGBRIGHT_KPH-1608CGCK")
        (field (name "MANUFACTURER") "KINGBRIGHT")
        (field (name "AUTHOR") "CERN DEM JLC")
      )
      (libsource (lib "ICs And Semiconductors") (part "LED Green 1C 2A"))
    )
    (comp (ref "LD3")
      (value "Green")
      (footprint "LED_KINGBRIGHT_KPH-1608CGCK")
      (description "LED Green 1C 2A")
      (fields
        (field (name "PART NUMBER") "LED_KINGBRIGHT_KPH-1608CGCK")
        (field (name "MANUFACTURER") "KINGBRIGHT")
        (field (name "AUTHOR") "CERN DEM JLC")
      )
      (libsource (lib "ICs And Semiconductors") (part "LED Green 1C 2A"))
    )
    (comp (ref "LD4")
      (value "Green")
      (footprint "LED_KINGBRIGHT_KPH-1608CGCK")
      (description "LED Green 1C 2A")
      (fields
        (field (name "PART NUMBER") "LED_KINGBRIGHT_KPH-1608CGCK")
        (field (name "MANUFACTURER") "KINGBRIGHT")
        (field (name "AUTHOR") "CERN DEM JLC")
      )
      (libsource (lib "ICs And Semiconductors") (part "LED Green 1C 2A"))
    )
    (comp (ref "LD7")
      (value "Red")
      (footprint "LED_DIALIGHT_555-200")
      (description "LED Red 1C 2A")
      (fields
        (field (name "PART NUMBER") "LED_DIALIGHT_555-2001F")
        (field (name "MANUFACTURER") "DIALIGHT")
        (field (name "AUTHOR") "CERN DEM JMW")
      )
      (libsource (lib "ICs And Semiconductors") (part "LED Red 1C 2A"))
    )
    (comp (ref "LD8")
      (value "Green")
      (footprint "LED_KINGBRIGHT_KPH-1608CGCK")
      (description "LED Green 1C 2A")
      (fields
        (field (name "PART NUMBER") "LED_KINGBRIGHT_KPH-1608CGCK")
        (field (name "MANUFACTURER") "KINGBRIGHT")
        (field (name "AUTHOR") "CERN DEM JLC")
      )
      (libsource (lib "ICs And Semiconductors") (part "LED Green 1C 2A"))
    )
    (comp (ref "LD10")
      (value "Green")
      (footprint "LED_KINGBRIGHT_KPH-1608CGCK")
      (description "LED Green 1C 2A")
      (fields
        (field (name "PART NUMBER") "LED_KINGBRIGHT_KPH-1608CGCK")
        (field (name "MANUFACTURER") "KINGBRIGHT")
        (field (name "AUTHOR") "CERN DEM JLC")
      )
      (libsource (lib "ICs And Semiconductors") (part "LED Green 1C 2A"))
    )
    (comp (ref "LD11")
      (value "Green")
      (footprint "LED_KINGBRIGHT_KPH-1608CGCK")
      (description "LED Green 1C 2A")
      (fields
        (field (name "PART NUMBER") "LED_KINGBRIGHT_KPH-1608CGCK")
        (field (name "MANUFACTURER") "KINGBRIGHT")
        (field (name "AUTHOR") "CERN DEM JLC")
      )
      (libsource (lib "ICs And Semiconductors") (part "LED Green 1C 2A"))
    )
    (comp (ref "R1")
      (value "2k2")
      (footprint "RESC1005X40N")
      (description "Resistor - 1%")
      (fields
        (field (name "TOLERANCE") "±1%")
        (field (name "PART NUMBER") "R0402_2K2_1%_0.0625W_100PPM")
        (field (name "POWER") "0.0625W")
        (field (name "AUTHOR") "CERN DEM JLC")
      )
      (libsource (lib "Resistors") (part "Resistor - 1%"))
    )
    (comp (ref "R4")
      (value "2k2")
      (footprint "RESC1005X40N")
      (description "Resistor - 1%")
      (fields
        (field (name "TOLERANCE") "±1%")
        (field (name "PART NUMBER") "R0402_2K2_1%_0.0625W_100PPM")
        (field (name "POWER") "0.0625W")
        (field (name "AUTHOR") "CERN DEM JLC")
      )
      (libsource (lib "Resistors") (part "Resistor - 1%"))
    )
    (comp (ref "R5")
      (value "3k9")
      (footprint "RESC1005X40N")
      (description "Resistor - 1%")
      (fields
        (field (name "TOLERANCE") "±1%")
        (field (name "PART NUMBER") "R0402_3K9_1%_0.0625W_100PPM")
        (field (name "POWER") "0.0625W")
        (field (name "AUTHOR") "CERN DEM JLC")
      )
      (libsource (lib "Resistors") (part "Resistor - 1%"))
    )
    (comp (ref "R6")
      (value "3k9")
      (footprint "RESC1005X40N")
      (description "Resistor - 1%")
      (fields
        (field (name "TOLERANCE") "±1%")
        (field (name "PART NUMBER") "R0402_3K9_1%_0.0625W_100PPM")
        (field (name "POWER") "0.0625W")
        (field (name "AUTHOR") "CERN DEM JLC")
      )
      (libsource (lib "Resistors") (part "Resistor - 1%"))
    )
    (comp (ref "R7")
      (value "10k")
      (footprint "RESC1005X40N")
      (description "Resistor - 1%")
      (fields
        (field (name "PART NUMBER") "R0402_10K_1%_0.0625W_100PPM")
        (field (name "POWER") "0.0625W")
        (field (name "AUTHOR") "CERN DEM JLC")
      )
      (libsource (lib "Resistors") (part "Resistor - 1%"))
    )
    (comp (ref "R8")
      (value "0")
      (footprint "RESC1005X40N")
      (description "Resistor")
      (fields
        (field (name "PART NUMBER") "R0402_0R_JUMPER")
        (field (name "MANUFACTURER") "GENERIC")
        (field (name "AUTHOR") "CERN DEM JLC")
      )
      (libsource (lib "Resistors") (part "Resistor"))
    )
    (comp (ref "R9")
      (value "24k")
      (footprint "RESC1005X40N")
      (description "Resistor - 1%")
      (fields
        (field (name "TOLERANCE") "±1%")
        (field (name "PART NUMBER") "R0402_24K_1%_0.0625W_100PPM")
        (field (name "POWER") "0.0625W")
        (field (name "AUTHOR") "CERN DEM JLC")
      )
      (libsource (lib "Resistors") (part "Resistor - 1%"))
    )
    (comp (ref "R19")
      (value "10k")
      (footprint "RESC1005X40N")
      (description "Resistor - 1%")
      (fields
        (field (name "PART NUMBER") "R0402_10K_1%_0.0625W_100PPM")
        (field (name "POWER") "0.0625W")
        (field (name "AUTHOR") "CERN DEM JLC")
      )
      (libsource (lib "Resistors") (part "Resistor - 1%"))
    )
    (comp (ref "R20")
      (value "6k2")
      (footprint "RESC1608X55N")
      (description "Resistor - 1%")
      (fields
        (field (name "TOLERANCE") "±1%")
        (field (name "PART NUMBER") "R0603_6K2_1%_0.1W_100PPM")
        (field (name "POWER") "0.1W")
        (field (name "AUTHOR") "CERN DEM JLC")
      )
      (libsource (lib "") (part "Resistor - 1%_1"))
    )
    (comp (ref "R21")
      (value "82")
      (footprint "RESC1005X40N")
      (description "Resistor - 1%")
      (fields
        (field (name "TOLERANCE") "±1%")
        (field (name "PART NUMBER") "R0402_82R_1%_0.0625W_100PPM")
        (field (name "POWER") "0.0625W")
        (field (name "AUTHOR") "CERN DEM JLC")
      )
      (libsource (lib "Resistors") (part "Resistor - 1%"))
    )
    (comp (ref "R24")
      (value "0R02")
      (footprint "RESC3216X80N")
      (description "Resistor - 1%")
      (fields
        (field (name "TOLERANCE") "±1%")
        (field (name "PART NUMBER") "R1206_0R02_1%_0.5W_100PPM")
        (field (name "POWER") "0.5W")
        (field (name "AUTHOR") "CERN DEM JLC")
      )
      (libsource (lib "") (part "Resistor - 1%_1"))
    )
    (comp (ref "R26")
      (value "1k2")
      (footprint "RESC1608X55N")
      (description "Resistor - 1%")
      (fields
        (field (name "TOLERANCE") "±1%")
        (field (name "PART NUMBER") "R0603_1K2_1%_0.1W_100PPM")
        (field (name "POWER") "0.1W")
        (field (name "AUTHOR") "CERN DEM JLC")
      )
      (libsource (lib "") (part "Resistor - 1%_1"))
    )
    (comp (ref "R28")
      (value "0R02")
      (footprint "RESC3216X80N")
      (description "Resistor - 1%")
      (fields
        (field (name "TOLERANCE") "±1%")
        (field (name "PART NUMBER") "R1206_0R02_1%_0.5W_100PPM")
        (field (name "POWER") "0.5W")
        (field (name "AUTHOR") "CERN DEM JLC")
      )
      (libsource (lib "") (part "Resistor - 1%_1"))
    )
    (comp (ref "R32")
      (value "1k6")
      (footprint "RESC1608X55N")
      (description "Resistor - 1%")
      (fields
        (field (name "TOLERANCE") "±1%")
        (field (name "PART NUMBER") "R0603_1K6_1%_0.1W_100PPM")
        (field (name "POWER") "0.1W")
        (field (name "AUTHOR") "CERN DEM JLC")
      )
      (libsource (lib "") (part "Resistor - 1%_1"))
    )
    (comp (ref "R33")
      (value "15k")
      (footprint "RESC1608X55N")
      (description "Resistor - 1%")
      (fields
        (field (name "TOLERANCE") "±1%")
        (field (name "PART NUMBER") "R0603_15K_1%_0.1W_100PPM")
        (field (name "POWER") "0.1W")
        (field (name "AUTHOR") "CERN DEM JMW")
      )
      (libsource (lib "") (part "Resistor - 1%_1"))
    )
    (comp (ref "R39")
      (value "33k")
      (footprint "RESC1608X55N")
      (description "Resistor - 1%")
      (fields
        (field (name "PART NUMBER") "R0603_33K_1%_0.1W_100PPM")
        (field (name "POWER") "0.1W")
        (field (name "AUTHOR") "CERN DEM JLC")
      )
      (libsource (lib "Resistors") (part "Resistor - 1%"))
    )
    (comp (ref "R40")
      (value "100k")
      (footprint "RESC1005X40N")
      (description "Resistor - 1%")
      (fields
        (field (name "PART NUMBER") "R0402_100K_1%_0.0625W_100PPM")
        (field (name "MANUFACTURER") "GENERIC")
        (field (name "AUTHOR") "CERN DEM JLC")
      )
      (libsource (lib "Resistors") (part "Resistor - 1%"))
    )
    (comp (ref "R41")
      (value "5k1")
      (footprint "RESC1608X55N")
      (description "Resistor - 1%")
      (fields
        (field (name "TOLERANCE") "±1%")
        (field (name "PART NUMBER") "R0603_5K1_1%_0.1W_100PPM")
        (field (name "POWER") "0.1W")
        (field (name "AUTHOR") "CERN DEM JLC")
      )
      (libsource (lib "") (part "Resistor - 1%_1"))
    )
    (comp (ref "R42")
      (value "1k6")
      (footprint "RESC1608X55N")
      (description "Resistor - 1%")
      (fields
        (field (name "TOLERANCE") "±1%")
        (field (name "PART NUMBER") "R0603_1K6_1%_0.1W_100PPM")
        (field (name "POWER") "0.1W")
        (field (name "AUTHOR") "CERN DEM JLC")
      )
      (libsource (lib "") (part "Resistor - 1%_1"))
    )
    (comp (ref "R43")
      (value "51k")
      (footprint "RESC1608X55N")
      (description "Resistor - 1%")
      (fields
        (field (name "TOLERANCE") "±1%")
        (field (name "PART NUMBER") "R0603_51K_1%_0.1W_100PPM")
        (field (name "POWER") "0.1W")
        (field (name "AUTHOR") "CERN DEM JLC")
      )
      (libsource (lib "") (part "Resistor - 1%_1"))
    )
    (comp (ref "R47")
      (value "1k5")
      (footprint "RESC1005X40N")
      (description "Resistor - 1%")
      (fields
        (field (name "PART NUMBER") "R0402_1K5_1%_0.0625W_100PPM")
        (field (name "POWER") "0.0625W")
        (field (name "AUTHOR") "CERN DEM JLC")
      )
      (libsource (lib "Resistors") (part "Resistor - 1%"))
    )
    (comp (ref "R48")
      (value "22k")
      (footprint "RESC1005X40N")
      (description "Resistor - 1%")
      (fields
        (field (name "PART NUMBER") "R0402_22K_1%_0.0625W_100PPM")
        (field (name "POWER") "0.0625W")
        (field (name "AUTHOR") "CERN DEM JLC")
      )
      (libsource (lib "Resistors") (part "Resistor - 1%"))
    )
    (comp (ref "R49")
      (value "10k")
      (footprint "RESC1005X40N")
      (description "Resistor - 1%")
      (fields
        (field (name "PART NUMBER") "R0402_10K_1%_0.0625W_100PPM")
        (field (name "POWER") "0.0625W")
        (field (name "AUTHOR") "CERN DEM JLC")
      )
      (libsource (lib "Resistors") (part "Resistor - 1%"))
    )
    (comp (ref "R51")
      (value "49k9")
      (footprint "RESC1608X55N")
      (description "Resistor - 0.1%")
      (fields
        (field (name "PART NUMBER") "R0603_49K9_0.1%_0.063W_10PPM")
        (field (name "POWER") "0.063W")
        (field (name "AUTHOR") "CERN DEM JLC")
      )
      (libsource (lib "Resistors") (part "Resistor - 0.1%"))
    )
    (comp (ref "R56")
      (value "10k")
      (footprint "RESC1005X40N")
      (description "Resistor - 1%")
      (fields
        (field (name "PART NUMBER") "R0402_10K_1%_0.0625W_100PPM")
        (field (name "POWER") "0.0625W")
        (field (name "AUTHOR") "CERN DEM JLC")
      )
      (libsource (lib "Resistors") (part "Resistor - 1%"))
    )
    (comp (ref "R65")
      (value "2k2")
      (footprint "RESC1005X40N")
      (description "Resistor - 1%")
      (fields
        (field (name "TOLERANCE") "±1%")
        (field (name "PART NUMBER") "R0402_2K2_1%_0.0625W_100PPM")
        (field (name "POWER") "0.0625W")
        (field (name "AUTHOR") "CERN DEM JLC")
      )
      (libsource (lib "Resistors") (part "Resistor - 1%"))
    )
    (comp (ref "R100")
      (value "3k3")
      (footprint "RESC1608X55N")
      (description "Resistor - 1%")
      (fields
        (field (name "PART NUMBER") "R0603_3K3_1%_0.1W_100PPM")
        (field (name "POWER") "0.1W")
        (field (name "AUTHOR") "CERN DEM JLC")
      )
      (libsource (lib "Resistors") (part "Resistor - 1%"))
    )
    (comp (ref "R116")
      (value "49k9")
      (footprint "RESC1608X55N")
      (description "Resistor - 0.1%")
      (fields
        (field (name "PART NUMBER") "R0603_49K9_0.1%_0.063W_10PPM")
        (field (name "POWER") "0.063W")
        (field (name "AUTHOR") "CERN DEM JLC")
      )
      (libsource (lib "Resistors") (part "Resistor - 0.1%"))
    )
    (comp (ref "R117")
      (value "27k")
      (footprint "RESC1005X40N")
      (description "Resistor - 1%")
      (fields
        (field (name "PART NUMBER") "R0402_27K_1%_0.0625W_100PPM")
        (field (name "POWER") "0.0625W")
        (field (name "AUTHOR") "CERN DEM JLC")
      )
      (libsource (lib "Resistors") (part "Resistor - 1%"))
    )
    (comp (ref "R121")
      (value "200")
      (footprint "RESC1005X40N")
      (description "Resistor - 1%")
      (fields
        (field (name "TOLERANCE") "±1%")
        (field (name "PART NUMBER") "R0402_200R_1%_0.0625W_100PPM")
        (field (name "POWER") "0.0625W")
        (field (name "AUTHOR") "CERN DEM JLC")
      )
      (libsource (lib "Resistors") (part "Resistor - 1%"))
    )
    (comp (ref "R122")
      (value "10k")
      (footprint "RESC1005X40N")
      (description "Resistor - 1%")
      (fields
        (field (name "PART NUMBER") "R0402_10K_1%_0.0625W_100PPM")
        (field (name "POWER") "0.0625W")
        (field (name "AUTHOR") "CERN DEM JLC")
      )
      (libsource (lib "Resistors") (part "Resistor - 1%"))
    )
    (comp (ref "R124")
      (value "10k")
      (footprint "RESC1005X40N")
      (description "Resistor - 1%")
      (fields
        (field (name "PART NUMBER") "R0402_10K_1%_0.0625W_100PPM")
        (field (name "POWER") "0.0625W")
        (field (name "AUTHOR") "CERN DEM JLC")
      )
      (libsource (lib "Resistors") (part "Resistor - 1%"))
    )
    (comp (ref "R125")
      (value "10k")
      (footprint "RESC1005X40N")
      (description "Resistor - 1%")
      (fields
        (field (name "PART NUMBER") "R0402_10K_1%_0.0625W_100PPM")
        (field (name "POWER") "0.0625W")
        (field (name "AUTHOR") "CERN DEM JLC")
      )
      (libsource (lib "Resistors") (part "Resistor - 1%"))
    )
    (comp (ref "R126")
      (value "0")
      (footprint "RESC1005X40N")
      (description "Resistor")
      (fields
        (field (name "PART NUMBER") "R0402_0R_JUMPER")
        (field (name "MANUFACTURER") "GENERIC")
        (field (name "AUTHOR") "CERN DEM JLC")
      )
      (libsource (lib "Resistors") (part "Resistor"))
    )
    (comp (ref "R127")
      (value "0")
      (footprint "RESC1005X40N")
      (description "Resistor")
      (fields
        (field (name "PART NUMBER") "R0402_0R_JUMPER")
        (field (name "MANUFACTURER") "GENERIC")
        (field (name "AUTHOR") "CERN DEM JLC")
      )
      (libsource (lib "Resistors") (part "Resistor"))
    )
    (comp (ref "R128")
      (value "0")
      (footprint "RESC1005X40N")
      (description "Resistor")
      (fields
        (field (name "PART NUMBER") "R0402_0R_JUMPER")
        (field (name "MANUFACTURER") "GENERIC")
        (field (name "AUTHOR") "CERN DEM JLC")
      )
      (libsource (lib "Resistors") (part "Resistor"))
    )
    (comp (ref "R131")
      (value "10k")
      (footprint "RESC1005X40N")
      (description "Resistor - 1%")
      (fields
        (field (name "PART NUMBER") "R0402_10K_1%_0.0625W_100PPM")
        (field (name "POWER") "0.0625W")
        (field (name "AUTHOR") "CERN DEM JLC")
      )
      (libsource (lib "Resistors") (part "Resistor - 1%"))
    )
    (comp (ref "R135")
      (value "47k")
      (footprint "RESC1005X40N")
      (description "Resistor - 1%")
      (fields
        (field (name "PART NUMBER") "R0402_47K_1%_0.0625W_100PPM")
        (field (name "POWER") "0.0625W")
        (field (name "AUTHOR") "CERN DEM JLC")
      )
      (libsource (lib "Resistors") (part "Resistor - 1%"))
    )
    (comp (ref "R142")
      (value "27k")
      (footprint "RESC1005X40N")
      (description "Resistor - 1%")
      (fields
        (field (name "PART NUMBER") "R0402_27K_1%_0.0625W_100PPM")
        (field (name "POWER") "0.0625W")
        (field (name "AUTHOR") "CERN DEM JLC")
      )
      (libsource (lib "Resistors") (part "Resistor - 1%"))
    )
    (comp (ref "R167")
      (value "Undefined")
      (footprint "RESC1608X55N")
      (description "Resistor")
      (fields (field (name "PART NUMBER") "R0603_NO-VALUE") (field (name "AUTHOR") "CERN DEM JLC"))
      (libsource (lib "Resistors") (part "Resistor"))
    )
    (comp (ref "R232")
      (value "24k")
      (footprint "RESC1005X40N")
      (description "Resistor - 1%")
      (fields
        (field (name "TOLERANCE") "±1%")
        (field (name "PART NUMBER") "R0402_24K_1%_0.0625W_100PPM")
        (field (name "POWER") "0.0625W")
        (field (name "AUTHOR") "CERN DEM JLC")
      )
      (libsource (lib "Resistors") (part "Resistor - 1%"))
    )
    (comp (ref "T3")
      (value "BSH103")
      (footprint "SOT95P230X110-3N")
      (description "N-CHANNEL MOSFET WITH DIODE")
      (fields (field (name "MANUFACTURER") "NEXPERIA") (field (name "AUTHOR") "CERN DEM JLC"))
      (libsource (lib "ICs And Semiconductors") (part "N-MOSFET-D 1G 2S 3D"))
    )
    (comp (ref "T4")
      (value "BSH103")
      (footprint "SOT95P230X110-3N")
      (description "N-CHANNEL MOSFET WITH DIODE")
      (fields (field (name "MANUFACTURER") "NEXPERIA") (field (name "AUTHOR") "CERN DEM JLC"))
      (libsource (lib "ICs And Semiconductors") (part "N-MOSFET-D 1G 2S 3D"))
    )
    (comp (ref "T5")
      (value "BSH103")
      (footprint "SOT95P230X110-3N")
      (description "N-CHANNEL MOSFET WITH DIODE")
      (fields (field (name "MANUFACTURER") "NEXPERIA") (field (name "AUTHOR") "CERN DEM JLC"))
      (libsource (lib "ICs And Semiconductors") (part "N-MOSFET-D 1G 2S 3D"))
    )
    (comp (ref "TP1")
      (value "Test Point")
      (footprint "TPS127")
      (fields (field (name "PART NUMBER") "SMD_PAD_1.27X1.27MM") (field (name "AUTHOR") "CERN DEM JLC"))
      (libsource (lib "Eletro-mechanical") (part "Test Point"))
    )
    (comp (ref "TP2")
      (value "Test Point")
      (footprint "TPS127")
      (fields (field (name "PART NUMBER") "SMD_PAD_1.27X1.27MM") (field (name "AUTHOR") "CERN DEM JLC"))
      (libsource (lib "Eletro-mechanical") (part "Test Point"))
    )
    (comp (ref "TP3")
      (value "Test Point")
      (footprint "TPS127")
      (fields (field (name "PART NUMBER") "SMD_PAD_1.27X1.27MM") (field (name "AUTHOR") "CERN DEM JLC"))
      (libsource (lib "Eletro-mechanical") (part "Test Point"))
    )
    (comp (ref "TP4")
      (value "Test Point")
      (footprint "TPS127")
      (fields (field (name "PART NUMBER") "SMD_PAD_1.27X1.27MM") (field (name "AUTHOR") "CERN DEM JLC"))
      (libsource (lib "Eletro-mechanical") (part "Test Point"))
    )
    (comp (ref "TP8")
      (value "Test Point")
      (footprint "TPS127")
      (fields (field (name "PART NUMBER") "SMD_PAD_1.27X1.27MM") (field (name "AUTHOR") "CERN DEM JLC"))
      (libsource (lib "Eletro-mechanical") (part "Test Point"))
    )
    (comp (ref "TP9")
      (value "Test Point")
      (footprint "TPS127")
      (fields (field (name "PART NUMBER") "SMD_PAD_1.27X1.27MM") (field (name "AUTHOR") "CERN DEM JLC"))
      (libsource (lib "Eletro-mechanical") (part "Test Point"))
    )
    (comp (ref "TP10")
      (value "Test Point")
      (footprint "TPS127")
      (fields (field (name "PART NUMBER") "SMD_PAD_1.27X1.27MM") (field (name "AUTHOR") "CERN DEM JLC"))
      (libsource (lib "Eletro-mechanical") (part "Test Point"))
    )
    (comp (ref "TP11")
      (value "Test Point")
      (footprint "TPS127")
      (fields (field (name "PART NUMBER") "SMD_PAD_1.27X1.27MM") (field (name "AUTHOR") "CERN DEM JLC"))
      (libsource (lib "Eletro-mechanical") (part "Test Point"))
    )
    (comp (ref "TP12")
      (value "Test Point")
      (footprint "TPS127")
      (fields (field (name "PART NUMBER") "SMD_PAD_1.27X1.27MM") (field (name "AUTHOR") "CERN DEM JLC"))
      (libsource (lib "Eletro-mechanical") (part "Test Point"))
    )
    (comp (ref "TP13")
      (value "Test Point")
      (footprint "TPS127")
      (fields (field (name "PART NUMBER") "SMD_PAD_1.27X1.27MM") (field (name "AUTHOR") "CERN DEM JLC"))
      (libsource (lib "Eletro-mechanical") (part "Test Point"))
    )
    (comp (ref "TP14")
      (value "Test Point")
      (footprint "TPS127")
      (fields (field (name "PART NUMBER") "SMD_PAD_1.27X1.27MM") (field (name "AUTHOR") "CERN DEM JLC"))
      (libsource (lib "Eletro-mechanical") (part "Test Point"))
    )
    (comp (ref "TP15")
      (value "Test Point")
      (footprint "TPS127")
      (fields (field (name "PART NUMBER") "SMD_PAD_1.27X1.27MM") (field (name "AUTHOR") "CERN DEM JLC"))
      (libsource (lib "Eletro-mechanical") (part "Test Point"))
    )
    (comp (ref "TP16")
      (value "Test Point")
      (footprint "TPS127")
      (fields (field (name "PART NUMBER") "SMD_PAD_1.27X1.27MM") (field (name "AUTHOR") "CERN DEM JLC"))
      (libsource (lib "Eletro-mechanical") (part "Test Point"))
    )
  )
  (nets
    (net (code "2") (name "/P5V5A") (class "Default")
      (node (ref "C108") (pin "2") (pinfunction "2_2") (pintype "passive"))
      (node (ref "C136") (pin "2") (pinfunction "2_2") (pintype "passive"))
      (node (ref "C23") (pin "2") (pinfunction "2_2") (pintype "passive"))
      (node (ref "C3") (pin "2") (pinfunction "2_2") (pintype "passive"))
      (node (ref "IC30") (pin "1") (pinfunction "IN_1") (pintype "input"))
      (node (ref "IC30") (pin "2") (pinfunction "IN_2") (pintype "input"))
      (node (ref "IC9") (pin "1") (pinfunction "IN_1") (pintype "input"))
      (node (ref "IC9") (pin "2") (pinfunction "IN_2") (pintype "input"))
      (node (ref "L18") (pin "2") (pinfunction "2_2") (pintype "passive"))
      (node (ref "R49") (pin "1") (pinfunction "1_1") (pintype "passive"))
    )
    (net (code "3") (name "/PGOOD") (class "Default")
      (node (ref "IC21") (pin "4") (pinfunction "PG_4") (pintype "output"))
      (node (ref "IC3") (pin "4") (pinfunction "PG_4") (pintype "output"))
      (node (ref "IC30") (pin "4") (pinfunction "PG_4") (pintype "output"))
      (node (ref "IC36") (pin "B4") (pinfunction "PGOOD2_B4") (pintype "open_collector"))
      (node (ref "IC36") (pin "D4") (pinfunction "PGOOD1_D4") (pintype "open_collector"))
      (node (ref "IC4") (pin "1") (pinfunction "~{SHDN}_1") (pintype "input"))
      (node (ref "IC7") (pin "1") (pinfunction "~{SHDN}_1") (pintype "input"))
      (node (ref "IC8") (pin "4") (pinfunction "PG_4") (pintype "output"))
      (node (ref "IC9") (pin "4") (pinfunction "PG_4") (pintype "output"))
    )
    (net (code "4") (name "/PSU_EN") (class "Default")
      (node (ref "IC21") (pin "3") (pinfunction "EN/UV_3") (pintype "input"))
      (node (ref "IC36") (pin "B2") (pinfunction "RUN2_B2") (pintype "input"))
      (node (ref "IC36") (pin "D2") (pinfunction "RUN1_D2") (pintype "input"))
      (node (ref "IC8") (pin "3") (pinfunction "EN/UV_3") (pintype "input"))
      (node (ref "R19") (pin "1") (pinfunction "1_1") (pintype "passive"))
      (node (ref "T5") (pin "3") (pinfunction "D_3") (pintype "passive"))
    )
    (net (code "5") (name "/SCL") (class "Default")
      (node (ref "R128") (pin "1") (pinfunction "1_1") (pintype "passive"))
    )
    (net (code "6") (name "/SDA") (class "Default")
      (node (ref "R126") (pin "1") (pinfunction "1_1") (pintype "passive"))
    )
    (net (code "7") (name "/VCC_OSC1") (class "Default")
      (node (ref "C4") (pin "2") (pinfunction "2_2") (pintype "passive"))
      (node (ref "C5") (pin "2") (pinfunction "2_2") (pintype "passive"))
      (node (ref "C6") (pin "2") (pinfunction "2_2") (pintype "passive"))
      (node (ref "IC9") (pin "10") (pinfunction "OUT_10") (pintype "output"))
      (node (ref "IC9") (pin "9") (pinfunction "OUTS_9") (pintype "output"))
      (node (ref "R24") (pin "1") (pinfunction "1_1") (pintype "passive"))
      (node (ref "R48") (pin "2") (pinfunction "2_2") (pintype "passive"))
    )
    (net (code "8") (name "/VCC_OSC2") (class "Default")
      (node (ref "C117") (pin "2") (pinfunction "2_2") (pintype "passive"))
      (node (ref "C121") (pin "2") (pinfunction "2_2") (pintype "passive"))
      (node (ref "C122") (pin "2") (pinfunction "2_2") (pintype "passive"))
      (node (ref "IC30") (pin "10") (pinfunction "OUT_10") (pintype "output"))
      (node (ref "IC30") (pin "9") (pinfunction "OUTS_9") (pintype "output"))
      (node (ref "R28") (pin "1") (pinfunction "1_1") (pintype "passive"))
    )
    (net (code "10") (name "GND") (class "Default")
      (node (ref "C100") (pin "1") (pinfunction "1_1") (pintype "passive"))
      (node (ref "C101") (pin "2") (pinfunction "2_2") (pintype "passive"))
      (node (ref "C102") (pin "2") (pinfunction "2_2") (pintype "passive"))
      (node (ref "C103") (pin "1") (pinfunction "1_1") (pintype "passive"))
      (node (ref "C104") (pin "2") (pinfunction "2_2") (pintype "passive"))
      (node (ref "C108") (pin "1") (pinfunction "1_1") (pintype "passive"))
      (node (ref "C117") (pin "1") (pinfunction "1_1") (pintype "passive"))
      (node (ref "C121") (pin "1") (pinfunction "1_1") (pintype "passive"))
      (node (ref "C122") (pin "1") (pinfunction "1_1") (pintype "passive"))
      (node (ref "C123") (pin "2") (pinfunction "2_2") (pintype "passive"))
      (node (ref "C13") (pin "2") (pinfunction "2_2") (pintype "passive"))
      (node (ref "C134") (pin "1") (pinfunction "1_1") (pintype "passive"))
      (node (ref "C135") (pin "1") (pinfunction "1_1") (pintype "passive"))
      (node (ref "C136") (pin "1") (pinfunction "1_1") (pintype "passive"))
      (node (ref "C14") (pin "1") (pinfunction "1_1") (pintype "passive"))
      (node (ref "C154") (pin "1") (pinfunction "1_1") (pintype "passive"))
      (node (ref "C16") (pin "1") (pinfunction "1_1") (pintype "passive"))
      (node (ref "C17") (pin "1") (pinfunction "1_1") (pintype "passive"))
      (node (ref "C19") (pin "1") (pinfunction "1_1") (pintype "passive"))
      (node (ref "C2") (pin "1") (pinfunction "1_1") (pintype "passive"))
      (node (ref "C21") (pin "1") (pinfunction "1_1") (pintype "passive"))
      (node (ref "C23") (pin "1") (pinfunction "1_1") (pintype "passive"))
      (node (ref "C24") (pin "1") (pinfunction "1_1") (pintype "passive"))
      (node (ref "C26") (pin "2") (pinfunction "2_2") (pintype "passive"))
      (node (ref "C27") (pin "1") (pinfunction "1_1") (pintype "passive"))
      (node (ref "C28") (pin "1") (pinfunction "1_1") (pintype "passive"))
      (node (ref "C3") (pin "1") (pinfunction "1_1") (pintype "passive"))
      (node (ref "C30") (pin "1") (pinfunction "1_1") (pintype "passive"))
      (node (ref "C31") (pin "1") (pinfunction "1_1") (pintype "passive"))
      (node (ref "C32") (pin "2") (pinfunction "2_2") (pintype "passive"))
      (node (ref "C33") (pin "1") (pinfunction "1_1") (pintype "passive"))
      (node (ref "C35") (pin "2") (pinfunction "2_2") (pintype "passive"))
      (node (ref "C36") (pin "1") (pinfunction "1_1") (pintype "passive"))
      (node (ref "C38") (pin "1") (pinfunction "1_1") (pintype "passive"))
      (node (ref "C4") (pin "1") (pinfunction "1_1") (pintype "passive"))
      (node (ref "C5") (pin "1") (pinfunction "1_1") (pintype "passive"))
      (node (ref "C6") (pin "1") (pinfunction "1_1") (pintype "passive"))
      (node (ref "C65") (pin "1") (pinfunction "1_1") (pintype "passive"))
      (node (ref "C7") (pin "1") (pinfunction "1_1") (pintype "passive"))
      (node (ref "C73") (pin "1") (pinfunction "1_1") (pintype "passive"))
      (node (ref "C74") (pin "1") (pinfunction "1_1") (pintype "passive"))
      (node (ref "C75") (pin "2") (pinfunction "2_2") (pintype "passive"))
      (node (ref "C76") (pin "1") (pinfunction "1_1") (pintype "passive"))
      (node (ref "C77") (pin "2") (pinfunction "2_2") (pintype "passive"))
      (node (ref "C83") (pin "1") (pinfunction "1_1") (pintype "passive"))
      (node (ref "C85") (pin "2") (pinfunction "2_2") (pintype "passive"))
      (node (ref "C90") (pin "1") (pinfunction "1_1") (pintype "passive"))
      (node (ref "C91") (pin "2") (pinfunction "2_2") (pintype "passive"))
      (node (ref "C92") (pin "1") (pinfunction "1_1") (pintype "passive"))
      (node (ref "C93") (pin "2") (pinfunction "2_2") (pintype "passive"))
      (node (ref "C96") (pin "1") (pinfunction "1_1") (pintype "passive"))
      (node (ref "C98") (pin "2") (pinfunction "2_2") (pintype "passive"))
      (node (ref "D11") (pin "2") (pinfunction "A_2") (pintype "passive"))
      (node (ref "FL1") (pin "4") (pinfunction "CG_4") (pintype "passive"))
      (node (ref "IC13") (pin "4") (pinfunction "GND_4") (pintype "power_in"))
      (node (ref "IC13") (pin "5") (pinfunction "A2_5") (pintype "input"))
      (node (ref "IC13") (pin "6") (pinfunction "A1_6") (pintype "input"))
      (node (ref "IC13") (pin "7") (pinfunction "A0_7") (pintype "input"))
      (node (ref "IC15") (pin "2") (pinfunction "GND_2") (pintype "power_in"))
      (node (ref "IC2") (pin "2") (pinfunction "GND_2") (pintype "power_in"))
      (node (ref "IC21") (pin "11") (pinfunction "GND_11") (pintype "power_in"))
      (node (ref "IC21") (pin "5") (pinfunction "ILIM_5") (pintype "input"))
      (node (ref "IC21") (pin "8") (pinfunction "GND_8") (pintype "power_in"))
      (node (ref "IC3") (pin "11") (pinfunction "GND_11") (pintype "power_in"))
      (node (ref "IC3") (pin "5") (pinfunction "ILIM_5") (pintype "input"))
      (node (ref "IC3") (pin "8") (pinfunction "GND_8") (pintype "power_in"))
      (node (ref "IC30") (pin "11") (pinfunction "GND_11") (pintype "power_in"))
      (node (ref "IC30") (pin "5") (pinfunction "ILIM_5") (pintype "input"))
      (node (ref "IC30") (pin "8") (pinfunction "GND_8") (pintype "power_in"))
      (node (ref "IC36") (pin "B5") (pinfunction "GND_B5") (pintype "power_in"))
      (node (ref "IC36") (pin "C1") (pinfunction "GND_C1") (pintype "power_in"))
      (node (ref "IC36") (pin "C2") (pinfunction "GND_C2") (pintype "power_in"))
      (node (ref "IC36") (pin "C5") (pinfunction "SYNC/MODE_C5") (pintype "input"))
      (node (ref "IC36") (pin "D5") (pinfunction "GND_D5") (pintype "power_in"))
      (node (ref "IC4") (pin "3") (pinfunction "GND_3") (pintype "power_in"))
      (node (ref "IC4") (pin "4") (pinfunction "GND_4") (pintype "power_in"))
      (node (ref "IC4") (pin "5") (pinfunction "GND_5") (pintype "power_in"))
      (node (ref "IC4") (pin "8") (pinfunction "GND_8") (pintype "power_in"))
      (node (ref "IC7") (pin "3") (pinfunction "GND_3") (pintype "power_in"))
      (node (ref "IC7") (pin "4") (pinfunction "GND_4") (pintype "power_in"))
      (node (ref "IC7") (pin "5") (pinfunction "GND_5") (pintype "power_in"))
      (node (ref "IC7") (pin "8") (pinfunction "GND_8") (pintype "power_in"))
      (node (ref "IC8") (pin "11") (pinfunction "GND_11") (pintype "power_in"))
      (node (ref "IC8") (pin "5") (pinfunction "ILIM_5") (pintype "input"))
      (node (ref "IC8") (pin "8") (pinfunction "GND_8") (pintype "power_in"))
      (node (ref "IC9") (pin "11") (pinfunction "GND_11") (pintype "power_in"))
      (node (ref "IC9") (pin "5") (pinfunction "ILIM_5") (pintype "input"))
      (node (ref "IC9") (pin "8") (pinfunction "GND_8") (pintype "power_in"))
      (node (ref "LD1") (pin "1") (pinfunction "C_1") (pintype "passive"))
      (node (ref "LD10") (pin "1") (pinfunction "C_1") (pintype "passive"))
      (node (ref "LD11") (pin "1") (pinfunction "C_1") (pintype "passive"))
      (node (ref "LD2") (pin "1") (pinfunction "C_1") (pintype "passive"))
      (node (ref "LD3") (pin "1") (pinfunction "C_1") (pintype "passive"))
      (node (ref "LD4") (pin "1") (pinfunction "C_1") (pintype "passive"))
      (node (ref "LD8") (pin "1") (pinfunction "C_1") (pintype "passive"))
      (node (ref "R100") (pin "1") (pinfunction "1_1") (pintype "passive"))
      (node (ref "R116") (pin "1") (pinfunction "1_1") (pintype "passive"))
      (node (ref "R142") (pin "1") (pinfunction "1_1") (pintype "passive"))
      (node (ref "R21") (pin "1") (pinfunction "1_1") (pintype "passive"))
      (node (ref "R26") (pin "1") (pinfunction "1_1") (pintype "passive"))
      (node (ref "R32") (pin "1") (pinfunction "1_1") (pintype "passive"))
      (node (ref "R39") (pin "1") (pinfunction "1_1") (pintype "passive"))
      (node (ref "R41") (pin "1") (pinfunction "1_1") (pintype "passive"))
      (node (ref "R42") (pin "1") (pinfunction "1_1") (pintype "passive"))
      (node (ref "R47") (pin "1") (pinfunction "1_1") (pintype "passive"))
      (node (ref "R51") (pin "1") (pinfunction "1_1") (pintype "passive"))
      (node (ref "T3") (pin "2") (pinfunction "S_2") (pintype "passive"))
      (node (ref "T4") (pin "2") (pinfunction "S_2") (pintype "passive"))
      (node (ref "T5") (pin "2") (pinfunction "S_2") (pintype "passive"))
      (node (ref "TP3") (pin "1") (pinfunction "1_1") (pintype "bidirectional"))
      (node (ref "TP4") (pin "1") (pinfunction "1_1") (pintype "bidirectional"))
    )
    (net (code "11") (name "GNDF") (class "Default")
      (node (ref "CON1") (pin "1") (pinfunction "1_1") (pintype "bidirectional"))
      (node (ref "CON1") (pin "2") (pinfunction "2_2") (pintype "bidirectional"))
      (node (ref "FL1") (pin "3") (pinfunction "PSG_3") (pintype "passive"))
      (node (ref "J5") (pin "1") (pinfunction "1_1") (pintype "bidirectional"))
    )
    (net (code "12") (name "Net-(C19-Pad2)") (class "Default")
      (node (ref "C19") (pin "2") (pinfunction "2_2") (pintype "passive"))
      (node (ref "C75") (pin "1") (pinfunction "1_1") (pintype "passive"))
      (node (ref "IC36") (pin "A2") (pinfunction "VIN1_A2") (pintype "power_in"))
      (node (ref "IC36") (pin "B3") (pinfunction "VIN1_B3") (pintype "power_in"))
      (node (ref "IC36") (pin "D3") (pinfunction "VIN2_D3") (pintype "power_in"))
      (node (ref "IC36") (pin "E2") (pinfunction "VIN2_E2") (pintype "power_in"))
      (node (ref "L12") (pin "2") (pinfunction "2_2") (pintype "passive"))
    )
    (net (code "13") (name "Net-(C26-Pad1)") (class "Default")
      (node (ref "C26") (pin "1") (pinfunction "1_1") (pintype "passive"))
      (node (ref "C27") (pin "2") (pinfunction "2_2") (pintype "passive"))
      (node (ref "IC8") (pin "1") (pinfunction "IN_1") (pintype "input"))
      (node (ref "IC8") (pin "2") (pinfunction "IN_2") (pintype "input"))
      (node (ref "L8") (pin "2") (pinfunction "2_2") (pintype "passive"))
    )
    (net (code "14") (name "Net-(C65-Pad2)") (class "Default")
      (node (ref "C65") (pin "2") (pinfunction "2_2") (pintype "passive"))
      (node (ref "C77") (pin "1") (pinfunction "1_1") (pintype "passive"))
      (node (ref "L4") (pin "2") (pinfunction "2_2") (pintype "passive"))
      (node (ref "L6") (pin "1") (pinfunction "1_1") (pintype "passive"))
      (node (ref "L8") (pin "1") (pinfunction "1_1") (pintype "passive"))
    )
    (net (code "15") (name "Net-(C85-Pad1)") (class "Default")
      (node (ref "C85") (pin "1") (pinfunction "1_1") (pintype "passive"))
      (node (ref "C92") (pin "2") (pinfunction "2_2") (pintype "passive"))
      (node (ref "IC21") (pin "1") (pinfunction "IN_1") (pintype "input"))
      (node (ref "IC21") (pin "2") (pinfunction "IN_2") (pintype "input"))
      (node (ref "L6") (pin "2") (pinfunction "2_2") (pintype "passive"))
    )
    (net (code "16") (name "Net-(IC3-EN{slash}UV)") (class "Default")
      (node (ref "C102") (pin "1") (pinfunction "1_1") (pintype "passive"))
      (node (ref "C2") (pin "2") (pinfunction "2_2") (pintype "passive"))
      (node (ref "IC3") (pin "1") (pinfunction "IN_1") (pintype "input"))
      (node (ref "IC3") (pin "2") (pinfunction "IN_2") (pintype "input"))
      (node (ref "IC3") (pin "3") (pinfunction "EN/UV_3") (pintype "input"))
      (node (ref "L1") (pin "2") (pinfunction "2_2") (pintype "passive"))
    )
    (net (code "17") (name "Net-(IC3-PGFB)") (class "Default")
      (node (ref "IC3") (pin "6") (pinfunction "PGFB_6") (pintype "input"))
      (node (ref "R32") (pin "2") (pinfunction "2_2") (pintype "passive"))
      (node (ref "R33") (pin "1") (pinfunction "1_1") (pintype "passive"))
    )
    (net (code "18") (name "Net-(IC3-SET)") (class "Default")
      (node (ref "C101") (pin "1") (pinfunction "1_1") (pintype "passive"))
      (node (ref "IC3") (pin "7") (pinfunction "SET_7") (pintype "input"))
      (node (ref "R39") (pin "2") (pinfunction "2_2") (pintype "passive"))
    )
    (net (code "19") (name "Net-(IC4-VOUTS)") (class "Default")
      (node (ref "C36") (pin "2") (pinfunction "2_2") (pintype "passive"))
      (node (ref "IC4") (pin "6") (pinfunction "VOUTS_6") (pintype "power_in"))
      (node (ref "IC7") (pin "6") (pinfunction "VOUTS/NR_6") (pintype "power_in"))
      (node (ref "R8") (pin "1") (pinfunction "1_1") (pintype "passive"))
    )
    (net (code "20") (name "Net-(IC8-PGFB)") (class "Default")
      (node (ref "IC8") (pin "6") (pinfunction "PGFB_6") (pintype "input"))
      (node (ref "R42") (pin "2") (pinfunction "2_2") (pintype "passive"))
      (node (ref "R43") (pin "1") (pinfunction "1_1") (pintype "passive"))
    )
    (net (code "21") (name "Net-(IC8-SET)") (class "Default")
      (node (ref "C32") (pin "1") (pinfunction "1_1") (pintype "passive"))
      (node (ref "IC8") (pin "7") (pinfunction "SET_7") (pintype "input"))
      (node (ref "R40") (pin "2") (pinfunction "2_2") (pintype "passive"))
    )
    (net (code "22") (name "Net-(IC13-O.S.)") (class "Default")
      (node (ref "IC13") (pin "3") (pinfunction "O.S._3") (pintype "output"))
      (node (ref "R127") (pin "1") (pinfunction "1_1") (pintype "passive"))
    )
    (net (code "23") (name "Net-(IC13-SCL)") (class "Default")
      (node (ref "IC13") (pin "2") (pinfunction "SCL_2") (pintype "input"))
      (node (ref "R125") (pin "1") (pinfunction "1_1") (pintype "passive"))
      (node (ref "R128") (pin "2") (pinfunction "2_2") (pintype "passive"))
    )
    (net (code "24") (name "Net-(IC13-SDA)") (class "Default")
      (node (ref "IC13") (pin "1") (pinfunction "SDA_1") (pintype "bidirectional"))
      (node (ref "R124") (pin "1") (pinfunction "1_1") (pintype "passive"))
      (node (ref "R126") (pin "2") (pinfunction "2_2") (pintype "passive"))
    )
    (net (code "25") (name "Net-(IC21-PGFB)") (class "Default")
      (node (ref "IC21") (pin "6") (pinfunction "PGFB_6") (pintype "input"))
      (node (ref "R100") (pin "2") (pinfunction "2_2") (pintype "passive"))
      (node (ref "R135") (pin "1") (pinfunction "1_1") (pintype "passive"))
    )
    (net (code "26") (name "Net-(IC21-SET)") (class "Default")
      (node (ref "C91") (pin "1") (pinfunction "1_1") (pintype "passive"))
      (node (ref "IC21") (pin "7") (pinfunction "SET_7") (pintype "input"))
      (node (ref "R117") (pin "2") (pinfunction "2_2") (pintype "passive"))
    )
    (net (code "27") (name "Net-(IC30-EN{slash}UV)") (class "Default")
      (node (ref "IC30") (pin "3") (pinfunction "EN/UV_3") (pintype "input"))
      (node (ref "IC9") (pin "3") (pinfunction "EN/UV_3") (pintype "input"))
      (node (ref "R49") (pin "2") (pinfunction "2_2") (pintype "passive"))
    )
    (net (code "28") (name "Net-(IC30-PGFB)") (class "Default")
      (node (ref "IC30") (pin "6") (pinfunction "PGFB_6") (pintype "input"))
      (node (ref "IC9") (pin "6") (pinfunction "PGFB_6") (pintype "input"))
      (node (ref "R47") (pin "2") (pinfunction "2_2") (pintype "passive"))
      (node (ref "R48") (pin "1") (pinfunction "1_1") (pintype "passive"))
    )
    (net (code "29") (name "Net-(IC30-SET)") (class "Default")
      (node (ref "C123") (pin "1") (pinfunction "1_1") (pintype "passive"))
      (node (ref "C93") (pin "1") (pinfunction "1_1") (pintype "passive"))
      (node (ref "IC30") (pin "7") (pinfunction "SET_7") (pintype "input"))
      (node (ref "IC9") (pin "7") (pinfunction "SET_7") (pintype "input"))
      (node (ref "R116") (pin "2") (pinfunction "2_2") (pintype "passive"))
      (node (ref "R51") (pin "2") (pinfunction "2_2") (pintype "passive"))
    )
    (net (code "30") (name "Net-(IC36-FB1)") (class "Default")
      (node (ref "IC36") (pin "E4") (pinfunction "FB1_E4") (pintype "input"))
      (node (ref "R232") (pin "2") (pinfunction "2_2") (pintype "passive"))
      (node (ref "R9") (pin "2") (pinfunction "2_2") (pintype "passive"))
    )
    (net (code "31") (name "Net-(IC36-FB2)") (class "Default")
      (node (ref "IC36") (pin "A4") (pinfunction "FB2_A4") (pintype "input"))
      (node (ref "R20") (pin "2") (pinfunction "2_2") (pintype "passive"))
    )
    (net (code "32") (name "Net-(IC36-TRACK{slash}SS1)") (class "Default")
      (node (ref "C154") (pin "2") (pinfunction "2_2") (pintype "passive"))
      (node (ref "IC36") (pin "E3") (pinfunction "TRACK/SS1_E3") (pintype "input"))
    )
    (net (code "33") (name "Net-(IC36-TRACK{slash}SS2)") (class "Default")
      (node (ref "C76") (pin "2") (pinfunction "2_2") (pintype "passive"))
      (node (ref "IC36") (pin "A3") (pinfunction "TRACK/SS2_A3") (pintype "input"))
    )
    (net (code "34") (name "Net-(L1-Pad1)") (class "Default")
      (node (ref "L1") (pin "1") (pinfunction "1_1") (pintype "passive"))
      (node (ref "L2") (pin "2") (pinfunction "2_2") (pintype "passive"))
    )
    (net (code "35") (name "Net-(L17-Pad1)") (class "Default")
      (node (ref "L17") (pin "1") (pinfunction "1_1") (pintype "passive"))
      (node (ref "R167") (pin "2") (pinfunction "2_2") (pintype "passive"))
    )
    (net (code "36") (name "Net-(L17-Pad2)") (class "Default")
      (node (ref "L17") (pin "2") (pinfunction "2_2") (pintype "passive"))
      (node (ref "L18") (pin "1") (pinfunction "1_1") (pintype "passive"))
    )
    (net (code "37") (name "Net-(LD1-A)") (class "Default")
      (node (ref "LD1") (pin "2") (pinfunction "A_2") (pintype "passive"))
      (node (ref "R4") (pin "1") (pinfunction "1_1") (pintype "passive"))
    )
    (net (code "38") (name "Net-(LD2-A)") (class "Default")
      (node (ref "LD2") (pin "2") (pinfunction "A_2") (pintype "passive"))
      (node (ref "R5") (pin "1") (pinfunction "1_1") (pintype "passive"))
    )
    (net (code "39") (name "Net-(LD3-A)") (class "Default")
      (node (ref "LD3") (pin "2") (pinfunction "A_2") (pintype "passive"))
      (node (ref "R6") (pin "1") (pinfunction "1_1") (pintype "passive"))
    )
    (net (code "40") (name "Net-(LD4-A)") (class "Default")
      (node (ref "LD4") (pin "2") (pinfunction "A_2") (pintype "passive"))
      (node (ref "R7") (pin "1") (pinfunction "1_1") (pintype "passive"))
    )
    (net (code "41") (name "Net-(LD7-A)") (class "Default")
      (node (ref "LD7") (pin "2") (pinfunction "A_2") (pintype "passive"))
      (node (ref "R121") (pin "1") (pinfunction "1_1") (pintype "passive"))
    )
    (net (code "42") (name "Net-(LD7-C)") (class "Default")
      (node (ref "LD7") (pin "1") (pinfunction "C_1") (pintype "passive"))
      (node (ref "T3") (pin "3") (pinfunction "D_3") (pintype "passive"))
    )
    (net (code "43") (name "Net-(LD8-A)") (class "Default")
      (node (ref "LD8") (pin "2") (pinfunction "A_2") (pintype "passive"))
      (node (ref "R65") (pin "1") (pinfunction "1_1") (pintype "passive"))
    )
    (net (code "44") (name "Net-(LD10-A)") (class "Default")
      (node (ref "LD10") (pin "2") (pinfunction "A_2") (pintype "passive"))
      (node (ref "R131") (pin "1") (pinfunction "1_1") (pintype "passive"))
    )
    (net (code "45") (name "Net-(LD11-A)") (class "Default")
      (node (ref "LD11") (pin "2") (pinfunction "A_2") (pintype "passive"))
      (node (ref "R1") (pin "1") (pinfunction "1_1") (pintype "passive"))
    )
    (net (code "46") (name "Net-(R20-Pad1)") (class "Default")
      (node (ref "R20") (pin "1") (pinfunction "1_1") (pintype "passive"))
      (node (ref "R26") (pin "2") (pinfunction "2_2") (pintype "passive"))
    )
    (net (code "47") (name "Net-(R21-Pad2)") (class "Default")
      (node (ref "R21") (pin "2") (pinfunction "2_2") (pintype "passive"))
      (node (ref "R232") (pin "1") (pinfunction "1_1") (pintype "passive"))
      (node (ref "R9") (pin "1") (pinfunction "1_1") (pintype "passive"))
    )
    (net (code "48") (name "Net-(R40-Pad1)") (class "Default")
      (node (ref "R40") (pin "1") (pinfunction "1_1") (pintype "passive"))
      (node (ref "R41") (pin "2") (pinfunction "2_2") (pintype "passive"))
    )
    (net (code "49") (name "Net-(R117-Pad1)") (class "Default")
      (node (ref "R117") (pin "1") (pinfunction "1_1") (pintype "passive"))
      (node (ref "R142") (pin "2") (pinfunction "2_2") (pintype "passive"))
    )
    (net (code "50") (name "Net-(T3-G)") (class "Default")
      (node (ref "R122") (pin "1") (pinfunction "1_1") (pintype "passive"))
      (node (ref "T3") (pin "1") (pinfunction "G_1") (pintype "passive"))
      (node (ref "T4") (pin "3") (pinfunction "D_3") (pintype "passive"))
      (node (ref "T5") (pin "1") (pinfunction "G_1") (pintype "passive"))
    )
    (net (code "51") (name "Net-(T4-G)") (class "Default")
      (node (ref "R127") (pin "2") (pinfunction "2_2") (pintype "passive"))
      (node (ref "R56") (pin "1") (pinfunction "1_1") (pintype "passive"))
      (node (ref "T4") (pin "1") (pinfunction "G_1") (pintype "passive"))
    )
    (net (code "52") (name "P3V3") (class "Default")
      (node (ref "C103") (pin "2") (pinfunction "2_2") (pintype "passive"))
      (node (ref "C104") (pin "1") (pinfunction "1_1") (pintype "passive"))
      (node (ref "D3") (pin "2") (pinfunction "A_2") (pintype "passive"))
      (node (ref "IC15") (pin "5") (pinfunction "OUT_5") (pintype "power_in"))
      (node (ref "R65") (pin "2") (pinfunction "2_2") (pintype "passive"))
      (node (ref "TP12") (pin "1") (pinfunction "1_1") (pintype "bidirectional"))
    )
    (net (code "53") (name "P3V3A") (class "Default")
      (node (ref "C14") (pin "2") (pinfunction "2_2") (pintype "passive"))
      (node (ref "C16") (pin "2") (pinfunction "2_2") (pintype "passive"))
      (node (ref "C17") (pin "2") (pinfunction "2_2") (pintype "passive"))
      (node (ref "IC3") (pin "10") (pinfunction "OUT_10") (pintype "output"))
      (node (ref "IC3") (pin "9") (pinfunction "OUTS_9") (pintype "output"))
      (node (ref "R1") (pin "2") (pinfunction "2_2") (pintype "passive"))
      (node (ref "R33") (pin "2") (pinfunction "2_2") (pintype "passive"))
      (node (ref "TP2") (pin "1") (pinfunction "1_1") (pintype "bidirectional"))
    )
    (net (code "54") (name "P3V3_DIOT") (class "Default")
      (node (ref "C13") (pin "1") (pinfunction "1_1") (pintype "passive"))
      (node (ref "C135") (pin "2") (pinfunction "2_2") (pintype "passive"))
      (node (ref "D9") (pin "2") (pinfunction "A_2") (pintype "passive"))
      (node (ref "IC2") (pin "5") (pinfunction "OUT_5") (pintype "power_in"))
      (node (ref "R4") (pin "2") (pinfunction "2_2") (pintype "passive"))
      (node (ref "TP11") (pin "1") (pinfunction "1_1") (pintype "bidirectional"))
    )
    (net (code "55") (name "P3V3_MP") (class "Default")
      (node (ref "C33") (pin "2") (pinfunction "2_2") (pintype "passive"))
      (node (ref "D3") (pin "1") (pinfunction "C_1") (pintype "passive"))
      (node (ref "D9") (pin "1") (pinfunction "C_1") (pintype "passive"))
      (node (ref "IC13") (pin "8") (pinfunction "+VS_8") (pintype "power_in"))
      (node (ref "R121") (pin "2") (pinfunction "2_2") (pintype "passive"))
      (node (ref "R122") (pin "2") (pinfunction "2_2") (pintype "passive"))
      (node (ref "R124") (pin "2") (pinfunction "2_2") (pintype "passive"))
      (node (ref "R125") (pin "2") (pinfunction "2_2") (pintype "passive"))
      (node (ref "R19") (pin "2") (pinfunction "2_2") (pintype "passive"))
      (node (ref "R56") (pin "2") (pinfunction "2_2") (pintype "passive"))
      (node (ref "TP16") (pin "1") (pinfunction "1_1") (pintype "bidirectional"))
    )
    (net (code "56") (name "P3V6") (class "Default")
      (node (ref "C100") (pin "2") (pinfunction "2_2") (pintype "passive"))
      (node (ref "C73") (pin "2") (pinfunction "2_2") (pintype "passive"))
      (node (ref "IC15") (pin "1") (pinfunction "IN_1") (pintype "input"))
      (node (ref "IC15") (pin "3") (pinfunction "EN_3") (pintype "input"))
      (node (ref "IC36") (pin "D1") (pinfunction "VOUT1_D1") (pintype "power_in"))
      (node (ref "IC36") (pin "E1") (pinfunction "VOUT1_E1") (pintype "power_in"))
      (node (ref "L2") (pin "1") (pinfunction "1_1") (pintype "passive"))
      (node (ref "TP13") (pin "1") (pinfunction "1_1") (pintype "bidirectional"))
    )
    (net (code "57") (name "P5V0_VREF") (class "Default")
      (node (ref "C24") (pin "2") (pinfunction "2_2") (pintype "passive"))
      (node (ref "C35") (pin "1") (pinfunction "1_1") (pintype "passive"))
      (node (ref "C38") (pin "2") (pinfunction "2_2") (pintype "passive"))
      (node (ref "IC4") (pin "7") (pinfunction "VOUTF_7") (pintype "power_in"))
      (node (ref "IC7") (pin "7") (pinfunction "VOUTF_7") (pintype "power_in"))
      (node (ref "R8") (pin "2") (pinfunction "2_2") (pintype "passive"))
      (node (ref "TP15") (pin "1") (pinfunction "1_1") (pintype "bidirectional"))
    )
    (net (code "58") (name "P5V4A") (class "Default")
      (node (ref "C7") (pin "2") (pinfunction "2_2") (pintype "passive"))
      (node (ref "C83") (pin "2") (pinfunction "2_2") (pintype "passive"))
      (node (ref "C90") (pin "2") (pinfunction "2_2") (pintype "passive"))
      (node (ref "C96") (pin "2") (pinfunction "2_2") (pintype "passive"))
      (node (ref "IC21") (pin "10") (pinfunction "OUT_10") (pintype "output"))
      (node (ref "IC21") (pin "9") (pinfunction "OUTS_9") (pintype "output"))
      (node (ref "IC4") (pin "2") (pinfunction "VIN_2") (pintype "input"))
      (node (ref "IC7") (pin "2") (pinfunction "VIN_2") (pintype "input"))
      (node (ref "R135") (pin "2") (pinfunction "2_2") (pintype "passive"))
      (node (ref "R5") (pin "2") (pinfunction "2_2") (pintype "passive"))
      (node (ref "TP8") (pin "1") (pinfunction "1_1") (pintype "bidirectional"))
    )
    (net (code "59") (name "P5V5") (class "Default")
      (node (ref "C21") (pin "2") (pinfunction "2_2") (pintype "passive"))
      (node (ref "IC36") (pin "A1") (pinfunction "VOUT2_A1") (pintype "power_in"))
      (node (ref "IC36") (pin "B1") (pinfunction "VOUT2_B1") (pintype "power_in"))
      (node (ref "R167") (pin "1") (pinfunction "1_1") (pintype "passive"))
      (node (ref "TP14") (pin "1") (pinfunction "1_1") (pintype "bidirectional"))
    )
    (net (code "60") (name "P10V5A") (class "Default")
      (node (ref "C28") (pin "2") (pinfunction "2_2") (pintype "passive"))
      (node (ref "C30") (pin "2") (pinfunction "2_2") (pintype "passive"))
      (node (ref "C31") (pin "2") (pinfunction "2_2") (pintype "passive"))
      (node (ref "IC8") (pin "10") (pinfunction "OUT_10") (pintype "output"))
      (node (ref "IC8") (pin "9") (pinfunction "OUTS_9") (pintype "output"))
      (node (ref "R43") (pin "2") (pinfunction "2_2") (pintype "passive"))
      (node (ref "R7") (pin "2") (pinfunction "2_2") (pintype "passive"))
      (node (ref "TP10") (pin "1") (pinfunction "1_1") (pintype "bidirectional"))
    )
    (net (code "61") (name "P12V0") (class "Default")
      (node (ref "C74") (pin "2") (pinfunction "2_2") (pintype "passive"))
      (node (ref "C98") (pin "1") (pinfunction "1_1") (pintype "passive"))
      (node (ref "D11") (pin "1") (pinfunction "C_1") (pintype "passive"))
      (node (ref "FL1") (pin "2") (pinfunction "CB_2") (pintype "passive"))
      (node (ref "L12") (pin "1") (pinfunction "1_1") (pintype "passive"))
      (node (ref "L4") (pin "1") (pinfunction "1_1") (pintype "passive"))
      (node (ref "R131") (pin "2") (pinfunction "2_2") (pintype "passive"))
      (node (ref "TP1") (pin "1") (pinfunction "1_1") (pintype "bidirectional"))
    )
    (net (code "62") (name "P12V0F") (class "Default")
      (node (ref "CON1") (pin "3") (pinfunction "3_3") (pintype "bidirectional"))
      (node (ref "CON1") (pin "4") (pinfunction "4_4") (pintype "bidirectional"))
      (node (ref "FL1") (pin "1") (pinfunction "B_1") (pintype "passive"))
      (node (ref "J5") (pin "3") (pinfunction "3_3") (pintype "bidirectional"))
    )
    (net (code "63") (name "P12V0_DIOT") (class "Default")
      (node (ref "C134") (pin "2") (pinfunction "2_2") (pintype "passive"))
      (node (ref "IC2") (pin "1") (pinfunction "IN_1") (pintype "input"))
      (node (ref "IC2") (pin "3") (pinfunction "EN_3") (pintype "input"))
    )
    (net (code "64") (name "VCC_OSC") (class "Default")
      (node (ref "R24") (pin "2") (pinfunction "2_2") (pintype "passive"))
      (node (ref "R28") (pin "2") (pinfunction "2_2") (pintype "passive"))
      (node (ref "R6") (pin "2") (pinfunction "2_2") (pintype "passive"))
      (node (ref "TP9") (pin "1") (pinfunction "1_1") (pintype "bidirectional"))
    )
    (net (code "65") (name "unconnected-(IC2-BYP-Pad4)") (class "Default")
      (node (ref "IC2") (pin "4") (pinfunction "BYP_4") (pintype "passive+no_connect"))
    )
    (net (code "66") (name "unconnected-(IC15-BYP-Pad4)") (class "Default")
      (node (ref "IC15") (pin "4") (pinfunction "BYP_4") (pintype "passive+no_connect"))
    )
    (net (code "67") (name "unconnected-(IC36-COMP1-PadE5)") (class "Default")
      (node (ref "IC36") (pin "E5") (pinfunction "COMP1_E5") (pintype "input+no_connect"))
    )
    (net (code "68") (name "unconnected-(IC36-COMP2-PadA5)") (class "Default")
      (node (ref "IC36") (pin "A5") (pinfunction "COMP2_A5") (pintype "input+no_connect"))
    )
    (net (code "69") (name "unconnected-(IC36-FREQ-PadC4)") (class "Default")
      (node (ref "IC36") (pin "C4") (pinfunction "FREQ_C4") (pintype "input+no_connect"))
    )
    (net (code "70") (name "unconnected-(IC36-INTVCC-PadC3)") (class "Default")
      (node (ref "IC36") (pin "C3") (pinfunction "INTVCC_C3") (pintype "power_in"))
    )
    (net (code "71") (name "unconnected-(J5-Pad2)") (class "Default")
      (node (ref "J5") (pin "2") (pinfunction "2_2") (pintype "bidirectional"))
    )
  )
)
